# clouds_v30.net
KiCad netlist of a schematic drawn in EAGLE
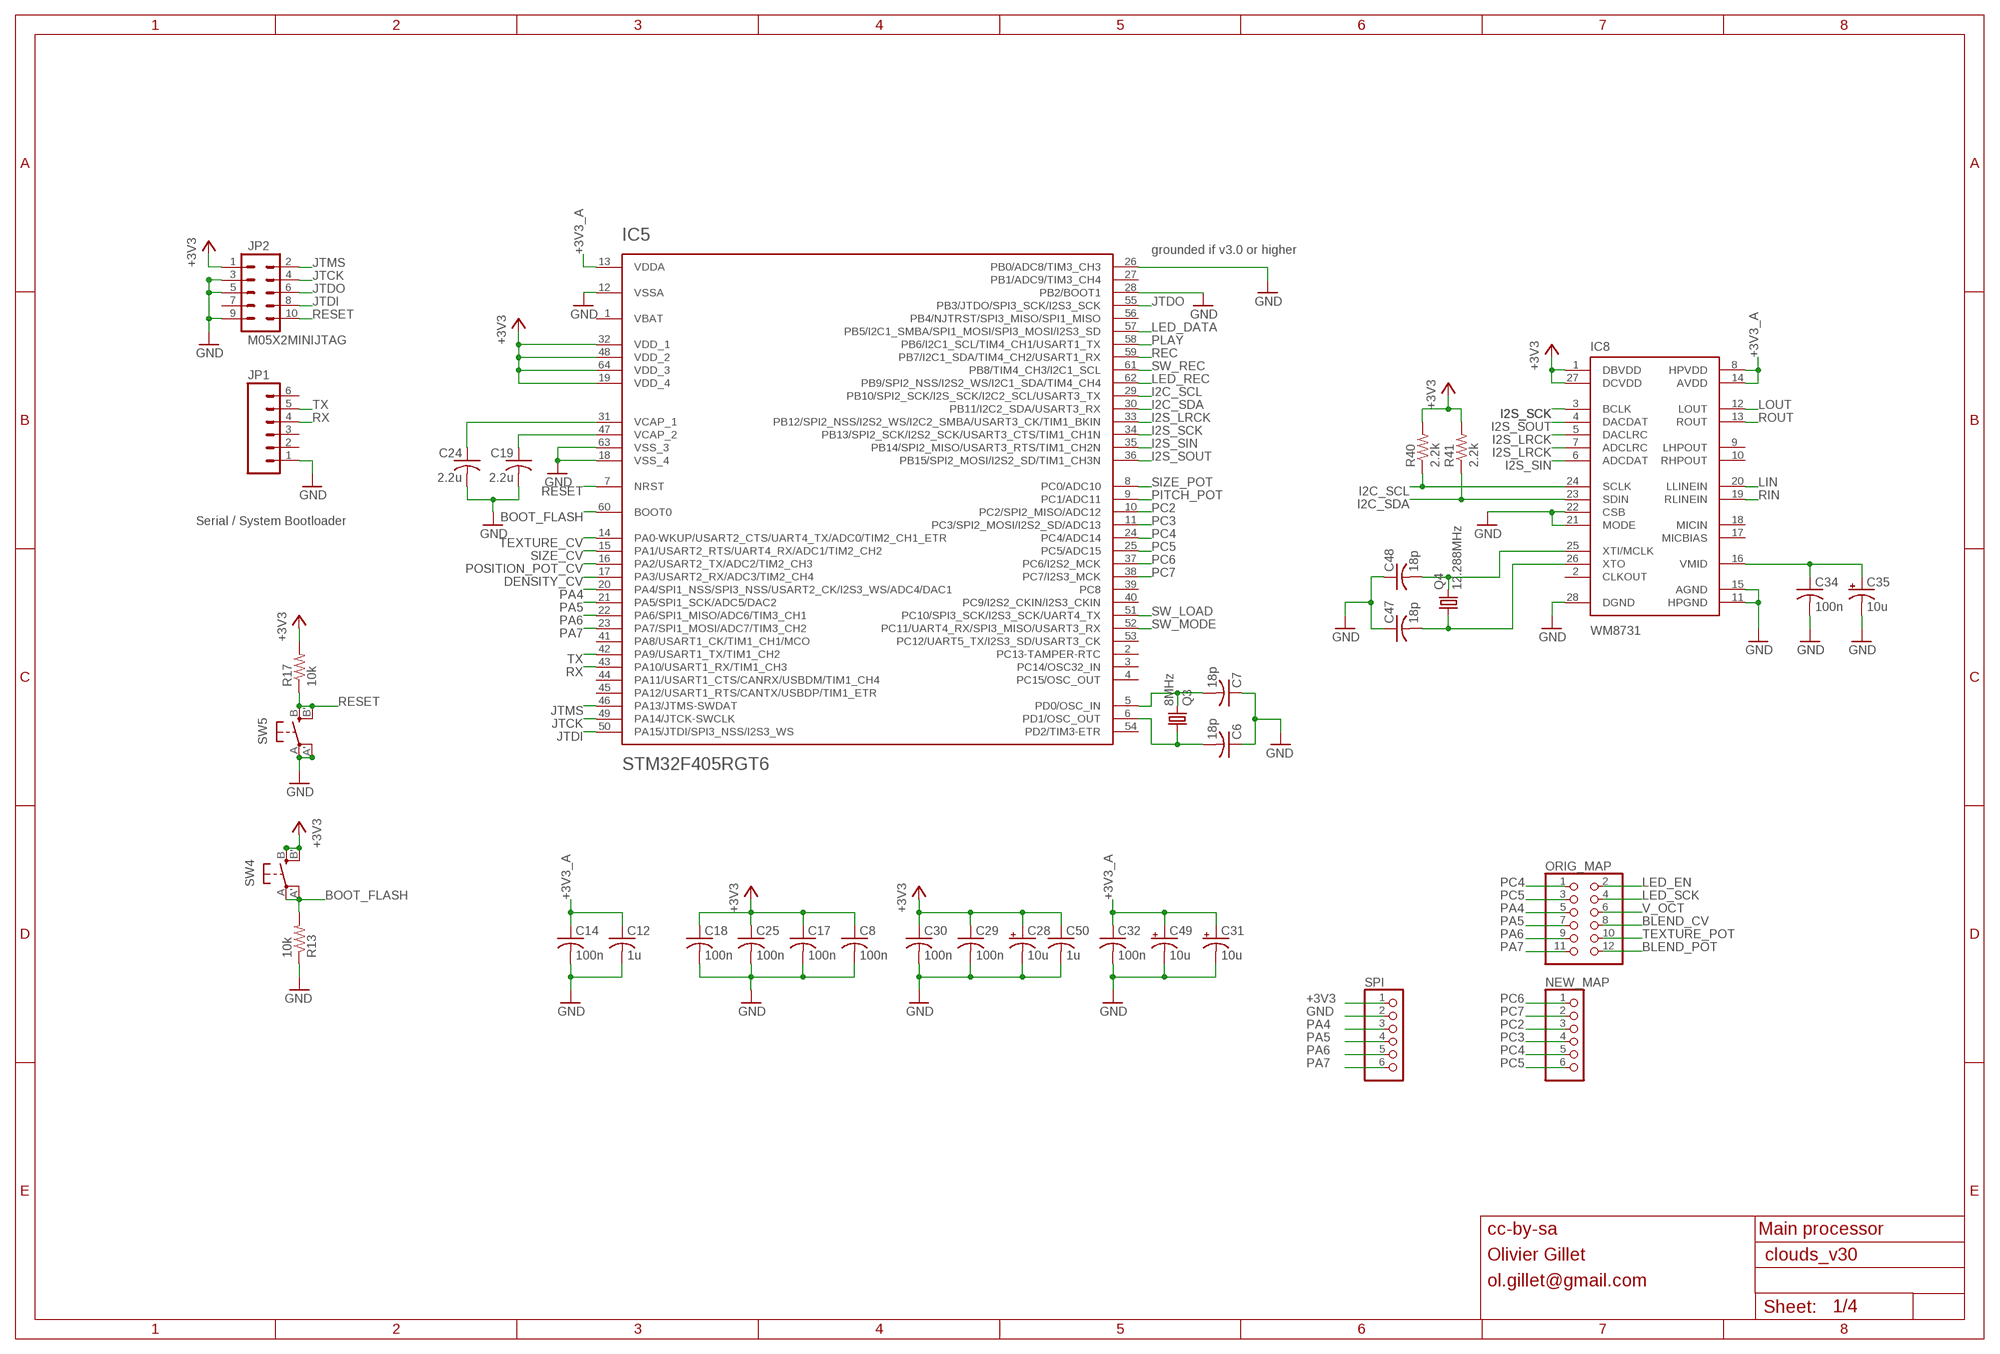
[diagram p0: schematic, sheet 1]
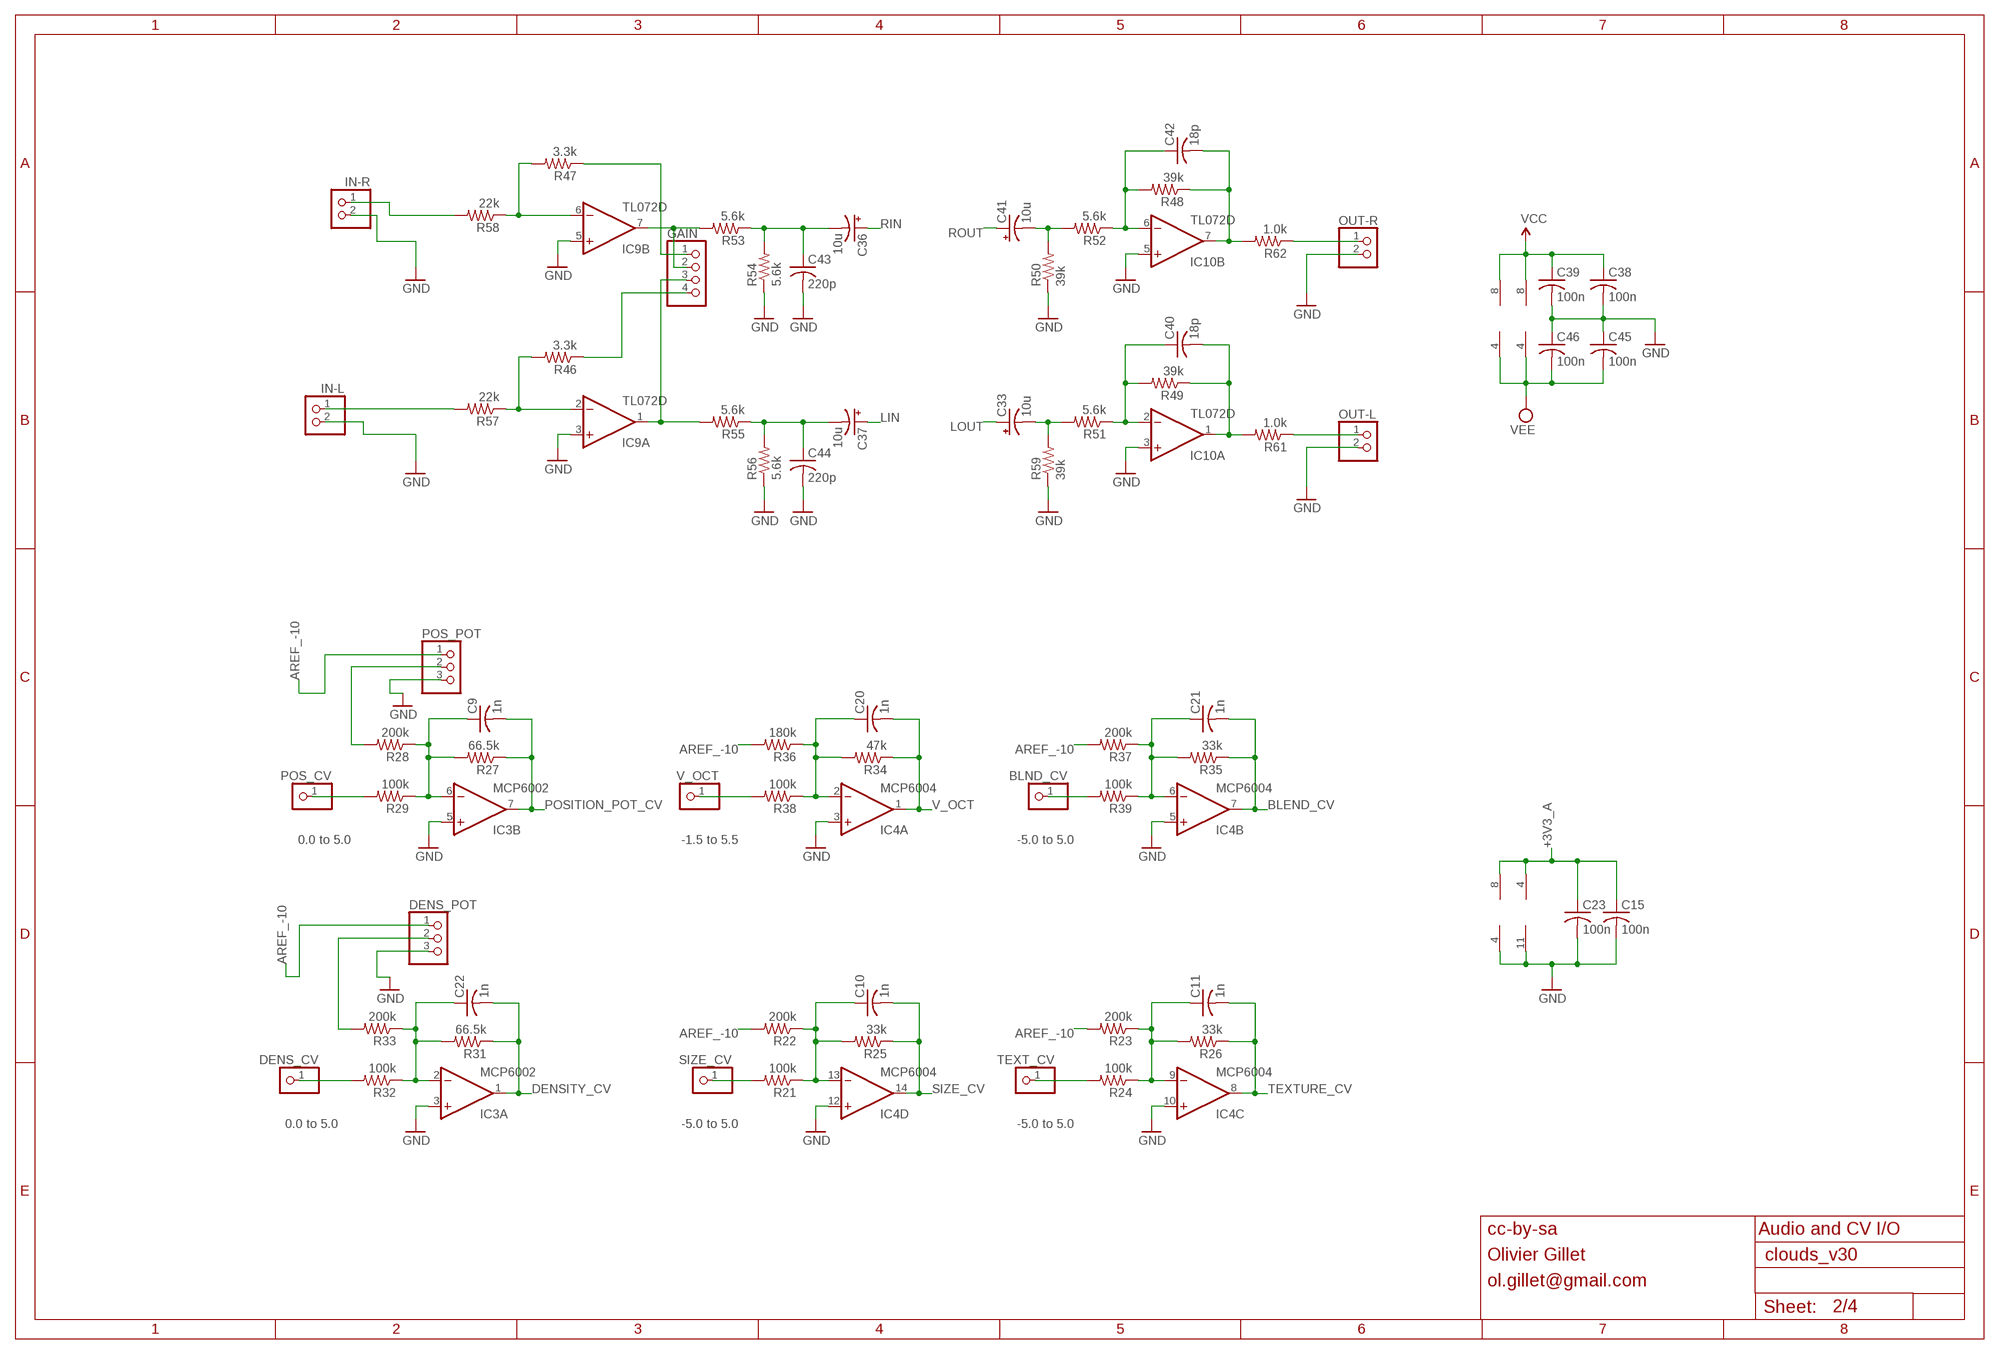
[diagram p1: schematic, sheet 2]
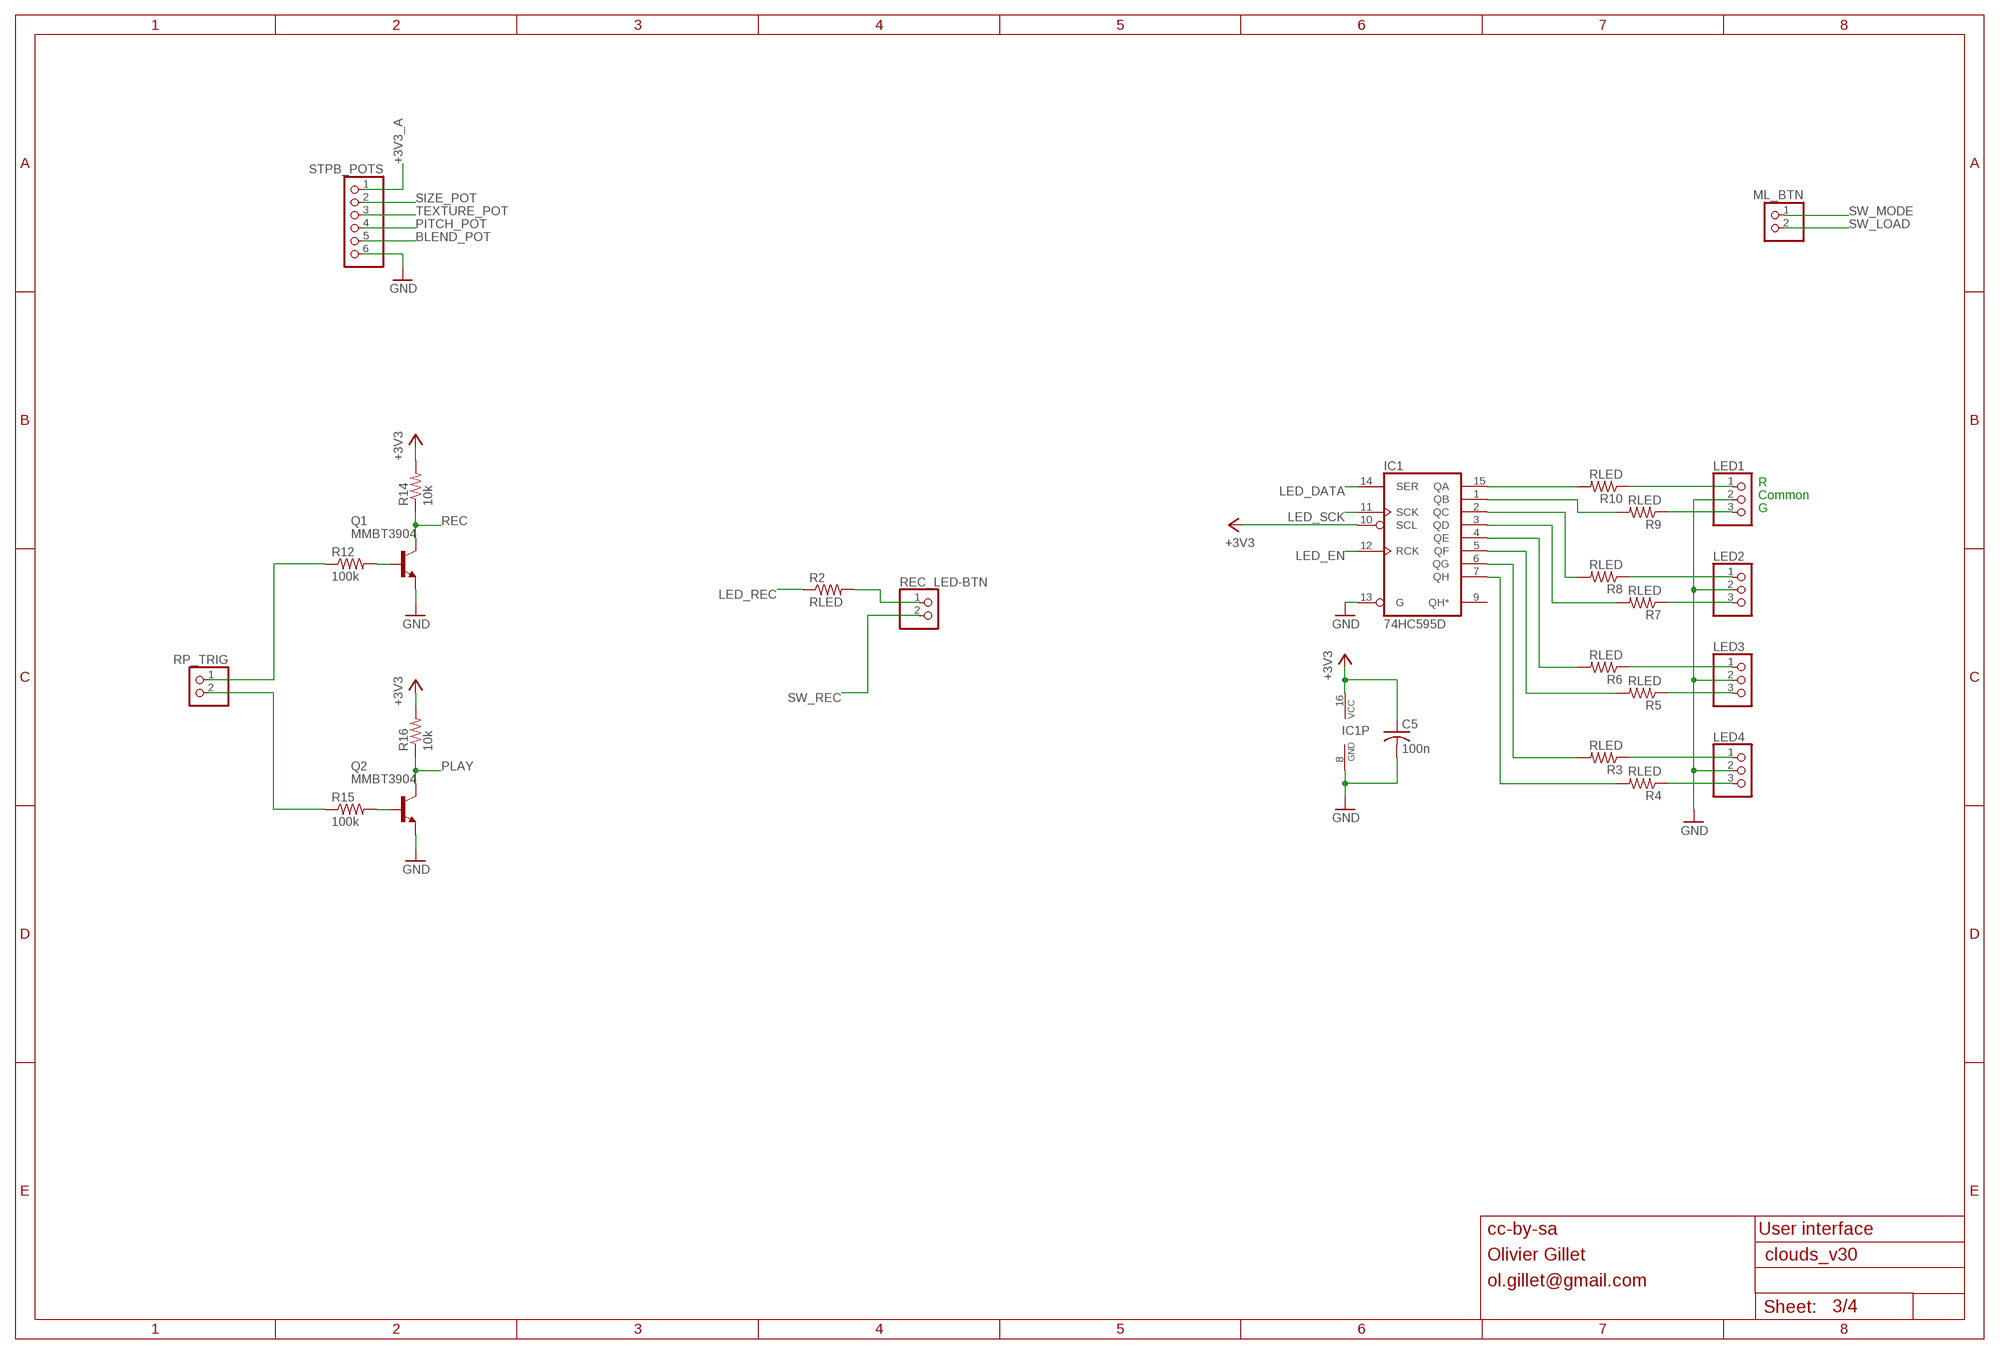
[diagram p2: schematic, sheet 3]
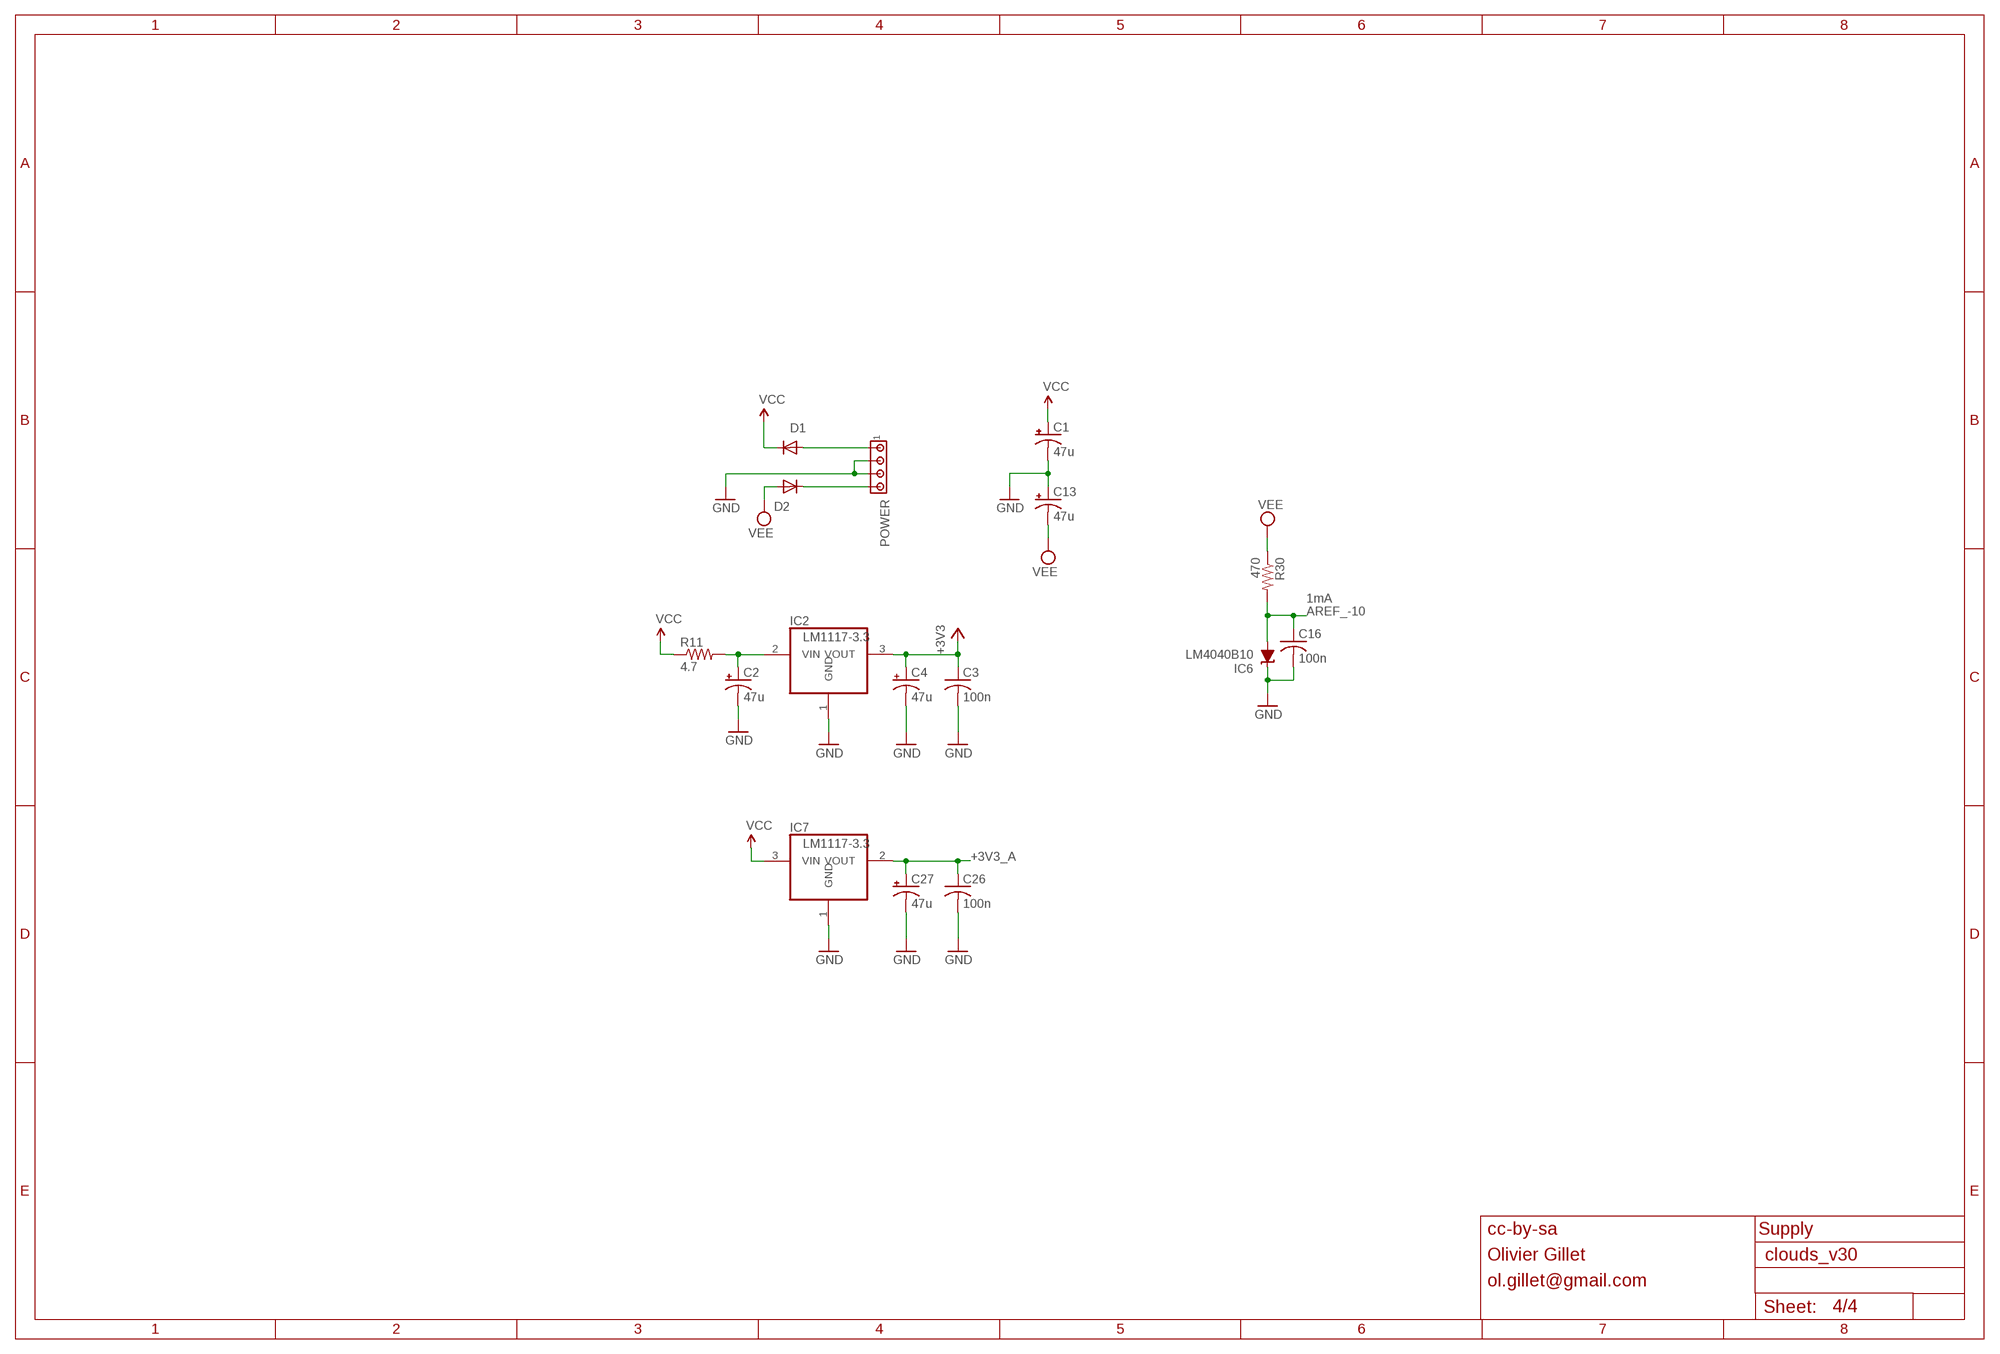
[diagram p3: schematic, sheet 4]

(export (version "E")
  (design (tool "Eeschema 10.0.6"))
  (components
    (comp (ref "C1")
      (value "47u")
      (footprint "eagle-import:PANASONIC_D")
      (libsource (lib "eagle-import") (part "CPOL-USD"))
    )
    (comp (ref "C2")
      (value "47u")
      (footprint "eagle-import:PANASONIC_D")
      (libsource (lib "eagle-import") (part "CPOL-USD"))
    )
    (comp (ref "C3")
      (value "100n")
      (footprint "eagle-import:C0603")
      (libsource (lib "eagle-import") (part "C-USC0603"))
    )
    (comp (ref "C4")
      (value "47u")
      (footprint "eagle-import:PANASONIC_D")
      (libsource (lib "eagle-import") (part "CPOL-USD"))
    )
    (comp (ref "C13")
      (value "47u")
      (footprint "eagle-import:PANASONIC_D")
      (libsource (lib "eagle-import") (part "CPOL-USD"))
    )
    (comp (ref "C16")
      (value "100n")
      (footprint "eagle-import:C0603")
      (libsource (lib "eagle-import") (part "C-USC0603"))
    )
    (comp (ref "C26")
      (value "100n")
      (footprint "eagle-import:C0603")
      (libsource (lib "eagle-import") (part "C-USC0603"))
    )
    (comp (ref "C27")
      (value "47u")
      (footprint "eagle-import:PANASONIC_D")
      (libsource (lib "eagle-import") (part "CPOL-USD"))
    )
    (comp (ref "D1")
      (value "1N5819HW")
      (footprint "eagle-import:SOD123")
      (libsource (lib "eagle-import") (part "DIODE-SOD123"))
    )
    (comp (ref "D2")
      (value "1N5819HW")
      (footprint "eagle-import:SOD123")
      (libsource (lib "eagle-import") (part "DIODE-SOD123"))
    )
    (comp (ref "IC2")
      (value "LM1117-3.3")
      (footprint "eagle-import:TO252")
      (libsource (lib "eagle-import") (part "REG1117T"))
    )
    (comp (ref "IC6")
      (value "LM4040B10")
      (footprint "eagle-import:DBZ_R-PDSO-G3")
      (libsource (lib "eagle-import") (part "LM4041DBZB12"))
    )
    (comp (ref "IC7")
      (value "LM1117-3.3")
      (footprint "eagle-import:SOT223")
      (libsource (lib "eagle-import") (part "REG1117"))
    )
    (comp (ref "POWER")
      (value "MTA04-156")
      (footprint "eagle-import:1X4MTA")
      (libsource (lib "eagle-import") (part "MTA04-156"))
    )
    (comp (ref "R11")
      (value "4.7")
      (footprint "eagle-import:R1206")
      (libsource (lib "eagle-import") (part "R-US_R1206"))
    )
    (comp (ref "R30")
      (value "470")
      (footprint "eagle-import:R0603")
      (libsource (lib "eagle-import") (part "R-US_R0603"))
    )
    (comp (ref "BLND_CV")
      (value "PINHD-1X1")
      (footprint "eagle-import:1X01")
      (libsource (lib "eagle-import") (part "PINHD-1X1"))
    )
    (comp (ref "C9")
      (value "1n")
      (footprint "eagle-import:C0603")
      (libsource (lib "eagle-import") (part "C-USC0603"))
    )
    (comp (ref "C10")
      (value "1n")
      (footprint "eagle-import:C0603")
      (libsource (lib "eagle-import") (part "C-USC0603"))
    )
    (comp (ref "C11")
      (value "1n")
      (footprint "eagle-import:C0603")
      (libsource (lib "eagle-import") (part "C-USC0603"))
    )
    (comp (ref "C15")
      (value "100n")
      (footprint "eagle-import:C0603")
      (libsource (lib "eagle-import") (part "C-USC0603"))
    )
    (comp (ref "C20")
      (value "1n")
      (footprint "eagle-import:C0603")
      (libsource (lib "eagle-import") (part "C-USC0603"))
    )
    (comp (ref "C21")
      (value "1n")
      (footprint "eagle-import:C0603")
      (libsource (lib "eagle-import") (part "C-USC0603"))
    )
    (comp (ref "C22")
      (value "1n")
      (footprint "eagle-import:C0603")
      (libsource (lib "eagle-import") (part "C-USC0603"))
    )
    (comp (ref "C23")
      (value "100n")
      (footprint "eagle-import:C0603")
      (libsource (lib "eagle-import") (part "C-USC0603"))
    )
    (comp (ref "C33")
      (value "10u")
      (footprint "eagle-import:PANASONIC_B")
      (libsource (lib "eagle-import") (part "CPOL-USB"))
    )
    (comp (ref "C36")
      (value "10u")
      (footprint "eagle-import:PANASONIC_B")
      (libsource (lib "eagle-import") (part "CPOL-USB"))
    )
    (comp (ref "C37")
      (value "10u")
      (footprint "eagle-import:PANASONIC_B")
      (libsource (lib "eagle-import") (part "CPOL-USB"))
    )
    (comp (ref "C38")
      (value "100n")
      (footprint "eagle-import:C0603")
      (libsource (lib "eagle-import") (part "C-USC0603"))
    )
    (comp (ref "C39")
      (value "100n")
      (footprint "eagle-import:C0603")
      (libsource (lib "eagle-import") (part "C-USC0603"))
    )
    (comp (ref "C40")
      (value "18p")
      (footprint "eagle-import:C0603")
      (libsource (lib "eagle-import") (part "C-USC0603"))
    )
    (comp (ref "C41")
      (value "10u")
      (footprint "eagle-import:PANASONIC_B")
      (libsource (lib "eagle-import") (part "CPOL-USB"))
    )
    (comp (ref "C42")
      (value "18p")
      (footprint "eagle-import:C0603")
      (libsource (lib "eagle-import") (part "C-USC0603"))
    )
    (comp (ref "C43")
      (value "220p")
      (footprint "eagle-import:C0603")
      (libsource (lib "eagle-import") (part "C-USC0603"))
    )
    (comp (ref "C44")
      (value "220p")
      (footprint "eagle-import:C0603")
      (libsource (lib "eagle-import") (part "C-USC0603"))
    )
    (comp (ref "C45")
      (value "100n")
      (footprint "eagle-import:C0603")
      (libsource (lib "eagle-import") (part "C-USC0603"))
    )
    (comp (ref "C46")
      (value "100n")
      (footprint "eagle-import:C0603")
      (libsource (lib "eagle-import") (part "C-USC0603"))
    )
    (comp (ref "DENS_CV")
      (value "PINHD-1X1")
      (footprint "eagle-import:1X01")
      (libsource (lib "eagle-import") (part "PINHD-1X1"))
    )
    (comp (ref "DENS_POT")
      (value "PINHD-1X3")
      (footprint "eagle-import:1X03")
      (libsource (lib "eagle-import") (part "PINHD-1X3"))
    )
    (comp (ref "GAIN")
      (value "PINHD-1X4")
      (footprint "eagle-import:1X04")
      (libsource (lib "eagle-import") (part "PINHD-1X4"))
    )
    (comp (ref "IC3")
      (value "MCP6002")
      (footprint "eagle-import:SO08")
      (libsource (lib "eagle-import") (part "TL072D"))
    )
    (comp (ref "IC4")
      (value "MCP6004")
      (footprint "eagle-import:SO14")
      (libsource (lib "eagle-import") (part "TL074D"))
    )
    (comp (ref "IC9")
      (value "TL072D")
      (footprint "eagle-import:SO08")
      (libsource (lib "eagle-import") (part "og-linear_TL072D"))
    )
    (comp (ref "IC10")
      (value "TL072D")
      (footprint "eagle-import:SO08")
      (libsource (lib "eagle-import") (part "og-linear_TL072D"))
    )
    (comp (ref "IN-L")
      (value "PINHD-1X2")
      (footprint "eagle-import:1X02")
      (libsource (lib "eagle-import") (part "PINHD-1X2"))
    )
    (comp (ref "IN-R")
      (value "PINHD-1X2")
      (footprint "eagle-import:1X02")
      (libsource (lib "eagle-import") (part "PINHD-1X2"))
    )
    (comp (ref "OUT-L")
      (value "PINHD-1X2")
      (footprint "eagle-import:1X02")
      (libsource (lib "eagle-import") (part "PINHD-1X2"))
    )
    (comp (ref "OUT-R")
      (value "PINHD-1X2")
      (footprint "eagle-import:1X02")
      (libsource (lib "eagle-import") (part "PINHD-1X2"))
    )
    (comp (ref "POS_CV")
      (value "PINHD-1X1")
      (footprint "eagle-import:1X01")
      (libsource (lib "eagle-import") (part "PINHD-1X1"))
    )
    (comp (ref "POS_POT")
      (value "PINHD-1X3")
      (footprint "eagle-import:1X03")
      (libsource (lib "eagle-import") (part "PINHD-1X3"))
    )
    (comp (ref "R21")
      (value "100k")
      (footprint "eagle-import:R0603")
      (libsource (lib "eagle-import") (part "R-US_R0603"))
    )
    (comp (ref "R22")
      (value "200k")
      (footprint "eagle-import:R0603")
      (libsource (lib "eagle-import") (part "R-US_R0603"))
    )
    (comp (ref "R23")
      (value "200k")
      (footprint "eagle-import:R0603")
      (libsource (lib "eagle-import") (part "R-US_R0603"))
    )
    (comp (ref "R24")
      (value "100k")
      (footprint "eagle-import:R0603")
      (libsource (lib "eagle-import") (part "R-US_R0603"))
    )
    (comp (ref "R25")
      (value "33k")
      (footprint "eagle-import:R0603")
      (libsource (lib "eagle-import") (part "R-US_R0603"))
    )
    (comp (ref "R26")
      (value "33k")
      (footprint "eagle-import:R0603")
      (libsource (lib "eagle-import") (part "R-US_R0603"))
    )
    (comp (ref "R27")
      (value "66.5k")
      (footprint "eagle-import:R0603")
      (libsource (lib "eagle-import") (part "R-US_R0603"))
    )
    (comp (ref "R28")
      (value "200k")
      (footprint "eagle-import:R0603")
      (libsource (lib "eagle-import") (part "R-US_R0603"))
    )
    (comp (ref "R29")
      (value "100k")
      (footprint "eagle-import:R0603")
      (libsource (lib "eagle-import") (part "R-US_R0603"))
    )
    (comp (ref "R31")
      (value "66.5k")
      (footprint "eagle-import:R0603")
      (libsource (lib "eagle-import") (part "R-US_R0603"))
    )
    (comp (ref "R32")
      (value "100k")
      (footprint "eagle-import:R0603")
      (libsource (lib "eagle-import") (part "R-US_R0603"))
    )
    (comp (ref "R33")
      (value "200k")
      (footprint "eagle-import:R0603")
      (libsource (lib "eagle-import") (part "R-US_R0603"))
    )
    (comp (ref "R34")
      (value "47k")
      (footprint "eagle-import:R0603")
      (libsource (lib "eagle-import") (part "R-US_R0603"))
    )
    (comp (ref "R35")
      (value "33k")
      (footprint "eagle-import:R0603")
      (libsource (lib "eagle-import") (part "R-US_R0603"))
    )
    (comp (ref "R36")
      (value "180k")
      (footprint "eagle-import:R0603")
      (libsource (lib "eagle-import") (part "R-US_R0603"))
    )
    (comp (ref "R37")
      (value "200k")
      (footprint "eagle-import:R0603")
      (libsource (lib "eagle-import") (part "R-US_R0603"))
    )
    (comp (ref "R38")
      (value "100k")
      (footprint "eagle-import:R0603")
      (libsource (lib "eagle-import") (part "R-US_R0603"))
    )
    (comp (ref "R39")
      (value "100k")
      (footprint "eagle-import:R0603")
      (libsource (lib "eagle-import") (part "R-US_R0603"))
    )
    (comp (ref "R46")
      (value "3.3k")
      (footprint "eagle-import:R0603")
      (libsource (lib "eagle-import") (part "R-US_R0603"))
    )
    (comp (ref "R47")
      (value "3.3k")
      (footprint "eagle-import:R0603")
      (libsource (lib "eagle-import") (part "R-US_R0603"))
    )
    (comp (ref "R48")
      (value "39k")
      (footprint "eagle-import:R0603")
      (libsource (lib "eagle-import") (part "R-US_R0603"))
    )
    (comp (ref "R49")
      (value "39k")
      (footprint "eagle-import:R0603")
      (libsource (lib "eagle-import") (part "R-US_R0603"))
    )
    (comp (ref "R50")
      (value "39k")
      (footprint "eagle-import:R0603")
      (libsource (lib "eagle-import") (part "R-US_R0603"))
    )
    (comp (ref "R51")
      (value "5.6k")
      (footprint "eagle-import:R0603")
      (libsource (lib "eagle-import") (part "R-US_R0603"))
    )
    (comp (ref "R52")
      (value "5.6k")
      (footprint "eagle-import:R0603")
      (libsource (lib "eagle-import") (part "R-US_R0603"))
    )
    (comp (ref "R53")
      (value "5.6k")
      (footprint "eagle-import:R0603")
      (libsource (lib "eagle-import") (part "R-US_R0603"))
    )
    (comp (ref "R54")
      (value "5.6k")
      (footprint "eagle-import:R0603")
      (libsource (lib "eagle-import") (part "R-US_R0603"))
    )
    (comp (ref "R55")
      (value "5.6k")
      (footprint "eagle-import:R0603")
      (libsource (lib "eagle-import") (part "R-US_R0603"))
    )
    (comp (ref "R56")
      (value "5.6k")
      (footprint "eagle-import:R0603")
      (libsource (lib "eagle-import") (part "R-US_R0603"))
    )
    (comp (ref "R57")
      (value "22k")
      (footprint "eagle-import:R0603")
      (libsource (lib "eagle-import") (part "R-US_R0603"))
    )
    (comp (ref "R58")
      (value "22k")
      (footprint "eagle-import:R0603")
      (libsource (lib "eagle-import") (part "R-US_R0603"))
    )
    (comp (ref "R59")
      (value "39k")
      (footprint "eagle-import:R0603")
      (libsource (lib "eagle-import") (part "R-US_R0603"))
    )
    (comp (ref "R61")
      (value "1.0k")
      (footprint "eagle-import:R0603")
      (libsource (lib "eagle-import") (part "R-US_R0603"))
    )
    (comp (ref "R62")
      (value "1.0k")
      (footprint "eagle-import:R0603")
      (libsource (lib "eagle-import") (part "R-US_R0603"))
    )
    (comp (ref "SIZE_CV")
      (value "PINHD-1X1")
      (footprint "eagle-import:1X01")
      (libsource (lib "eagle-import") (part "PINHD-1X1"))
    )
    (comp (ref "TEXT_CV")
      (value "PINHD-1X1")
      (footprint "eagle-import:1X01")
      (libsource (lib "eagle-import") (part "PINHD-1X1"))
    )
    (comp (ref "V_OCT")
      (value "PINHD-1X1")
      (footprint "eagle-import:1X01")
      (libsource (lib "eagle-import") (part "PINHD-1X1"))
    )
    (comp (ref "C6")
      (value "18p")
      (footprint "eagle-import:C0603")
      (libsource (lib "eagle-import") (part "C-USC0603"))
    )
    (comp (ref "C7")
      (value "18p")
      (footprint "eagle-import:C0603")
      (libsource (lib "eagle-import") (part "C-USC0603"))
    )
    (comp (ref "C8")
      (value "100n")
      (footprint "eagle-import:C0603")
      (libsource (lib "eagle-import") (part "C-USC0603"))
    )
    (comp (ref "C12")
      (value "1u")
      (footprint "eagle-import:C0603")
      (libsource (lib "eagle-import") (part "C-USC0603"))
    )
    (comp (ref "C14")
      (value "100n")
      (footprint "eagle-import:C0603")
      (libsource (lib "eagle-import") (part "C-USC0603"))
    )
    (comp (ref "C17")
      (value "100n")
      (footprint "eagle-import:C0603")
      (libsource (lib "eagle-import") (part "C-USC0603"))
    )
    (comp (ref "C18")
      (value "100n")
      (footprint "eagle-import:C0603")
      (libsource (lib "eagle-import") (part "C-USC0603"))
    )
    (comp (ref "C19")
      (value "2.2u")
      (footprint "eagle-import:C0805")
      (libsource (lib "eagle-import") (part "C-USC0805"))
    )
    (comp (ref "C24")
      (value "2.2u")
      (footprint "eagle-import:C0805")
      (libsource (lib "eagle-import") (part "C-USC0805"))
    )
    (comp (ref "C25")
      (value "100n")
      (footprint "eagle-import:C0603")
      (libsource (lib "eagle-import") (part "C-USC0603"))
    )
    (comp (ref "C28")
      (value "10u")
      (footprint "eagle-import:PANASONIC_A")
      (libsource (lib "eagle-import") (part "CPOL-USA"))
    )
    (comp (ref "C29")
      (value "100n")
      (footprint "eagle-import:C0603")
      (libsource (lib "eagle-import") (part "C-USC0603"))
    )
    (comp (ref "C30")
      (value "100n")
      (footprint "eagle-import:C0603")
      (libsource (lib "eagle-import") (part "C-USC0603"))
    )
    (comp (ref "C31")
      (value "10u")
      (footprint "eagle-import:PANASONIC_B")
      (libsource (lib "eagle-import") (part "CPOL-USB"))
    )
    (comp (ref "C32")
      (value "100n")
      (footprint "eagle-import:C0603")
      (libsource (lib "eagle-import") (part "C-USC0603"))
    )
    (comp (ref "C34")
      (value "100n")
      (footprint "eagle-import:C0603")
      (libsource (lib "eagle-import") (part "C-USC0603"))
    )
    (comp (ref "C35")
      (value "10u")
      (footprint "eagle-import:PANASONIC_B")
      (libsource (lib "eagle-import") (part "CPOL-USB"))
    )
    (comp (ref "C47")
      (value "18p")
      (footprint "eagle-import:C0603")
      (libsource (lib "eagle-import") (part "C-USC0603"))
    )
    (comp (ref "C48")
      (value "18p")
      (footprint "eagle-import:C0603")
      (libsource (lib "eagle-import") (part "C-USC0603"))
    )
    (comp (ref "C49")
      (value "10u")
      (footprint "eagle-import:PANASONIC_A")
      (libsource (lib "eagle-import") (part "CPOL-USA"))
    )
    (comp (ref "C50")
      (value "1u")
      (footprint "eagle-import:C0603")
      (libsource (lib "eagle-import") (part "C-USC0603"))
    )
    (comp (ref "IC5")
      (value "STM32F405RGT6")
      (footprint "eagle-import:TQFP-10X10-64")
      (libsource (lib "eagle-import") (part "STM32F20X"))
    )
    (comp (ref "IC8")
      (value "WM8731")
      (footprint "eagle-import:SSOP28")
      (libsource (lib "eagle-import") (part "WM8731"))
    )
    (comp (ref "JP1")
      (value "M06SIP")
      (footprint "eagle-import:1X06")
      (libsource (lib "eagle-import") (part "M06SIP"))
    )
    (comp (ref "JP2")
      (value "M05X2MINIJTAG")
      (footprint "eagle-import:2X5-1.27")
      (libsource (lib "eagle-import") (part "M05X2MINIJTAG"))
    )
    (comp (ref "NEW_MAP")
      (value "PINHD-1X6")
      (footprint "eagle-import:1X06")
      (libsource (lib "eagle-import") (part "PINHD-1X6"))
    )
    (comp (ref "ORIG_MAP")
      (value "PINHD-2X6")
      (footprint "eagle-import:2X06")
      (libsource (lib "eagle-import") (part "PINHD-2X6"))
    )
    (comp (ref "Q3")
      (value "8MHz")
      (footprint "eagle-import:HC49UP")
      (libsource (lib "eagle-import") (part "CRYSTALHC49UP"))
    )
    (comp (ref "Q4")
      (value "12.288MHz")
      (footprint "eagle-import:HC49UP")
      (libsource (lib "eagle-import") (part "CRYSTALHC49UP"))
    )
    (comp (ref "R13")
      (value "10k")
      (footprint "eagle-import:R0603")
      (libsource (lib "eagle-import") (part "R-US_R0603"))
    )
    (comp (ref "R17")
      (value "10k")
      (footprint "eagle-import:R0603")
      (libsource (lib "eagle-import") (part "R-US_R0603"))
    )
    (comp (ref "R40")
      (value "2.2k")
      (footprint "eagle-import:R0603")
      (libsource (lib "eagle-import") (part "R-US_R0603"))
    )
    (comp (ref "R41")
      (value "2.2k")
      (footprint "eagle-import:R0603")
      (libsource (lib "eagle-import") (part "R-US_R0603"))
    )
    (comp (ref "SPI")
      (value "PINHD-1X6")
      (footprint "eagle-import:1X06")
      (libsource (lib "eagle-import") (part "PINHD-1X6"))
    )
    (comp (ref "SW4")
      (value "EVQQ2")
      (footprint "eagle-import:EVQ-Q2")
      (libsource (lib "eagle-import") (part "EVQQ2"))
    )
    (comp (ref "SW5")
      (value "EVQQ2")
      (footprint "eagle-import:EVQ-Q2")
      (libsource (lib "eagle-import") (part "EVQQ2"))
    )
    (comp (ref "C5")
      (value "100n")
      (footprint "eagle-import:C0603")
      (libsource (lib "eagle-import") (part "C-USC0603"))
    )
    (comp (ref "IC1")
      (value "74HC595D")
      (footprint "eagle-import:SO16")
      (libsource (lib "eagle-import") (part "74595DHC"))
    )
    (comp (ref "LED1")
      (value "PINHD-1X3")
      (footprint "eagle-import:1X03")
      (libsource (lib "eagle-import") (part "PINHD-1X3"))
    )
    (comp (ref "LED2")
      (value "PINHD-1X3")
      (footprint "eagle-import:1X03")
      (libsource (lib "eagle-import") (part "PINHD-1X3"))
    )
    (comp (ref "LED3")
      (value "PINHD-1X3")
      (footprint "eagle-import:1X03")
      (libsource (lib "eagle-import") (part "PINHD-1X3"))
    )
    (comp (ref "LED4")
      (value "PINHD-1X3")
      (footprint "eagle-import:1X03")
      (libsource (lib "eagle-import") (part "PINHD-1X3"))
    )
    (comp (ref "ML_BTN")
      (value "PINHD-1X2")
      (footprint "eagle-import:1X02")
      (libsource (lib "eagle-import") (part "PINHD-1X2"))
    )
    (comp (ref "Q1")
      (value "MMBT3904")
      (footprint "eagle-import:SOT23-BEC")
      (libsource (lib "eagle-import") (part "-NPN-SOT23-BECMMBT3904LT1"))
    )
    (comp (ref "Q2")
      (value "MMBT3904")
      (footprint "eagle-import:SOT23-BEC")
      (libsource (lib "eagle-import") (part "-NPN-SOT23-BECMMBT3904LT1"))
    )
    (comp (ref "R2")
      (value "RLED")
      (footprint "eagle-import:R0603")
      (libsource (lib "eagle-import") (part "R-US_R0603"))
    )
    (comp (ref "R3")
      (value "RLED")
      (footprint "eagle-import:R0603")
      (libsource (lib "eagle-import") (part "R-US_R0603"))
    )
    (comp (ref "R4")
      (value "RLED")
      (footprint "eagle-import:R0603")
      (libsource (lib "eagle-import") (part "R-US_R0603"))
    )
    (comp (ref "R5")
      (value "RLED")
      (footprint "eagle-import:R0603")
      (libsource (lib "eagle-import") (part "R-US_R0603"))
    )
    (comp (ref "R6")
      (value "RLED")
      (footprint "eagle-import:R0603")
      (libsource (lib "eagle-import") (part "R-US_R0603"))
    )
    (comp (ref "R7")
      (value "RLED")
      (footprint "eagle-import:R0603")
      (libsource (lib "eagle-import") (part "R-US_R0603"))
    )
    (comp (ref "R8")
      (value "RLED")
      (footprint "eagle-import:R0603")
      (libsource (lib "eagle-import") (part "R-US_R0603"))
    )
    (comp (ref "R9")
      (value "RLED")
      (footprint "eagle-import:R0603")
      (libsource (lib "eagle-import") (part "R-US_R0603"))
    )
    (comp (ref "R10")
      (value "RLED")
      (footprint "eagle-import:R0603")
      (libsource (lib "eagle-import") (part "R-US_R0603"))
    )
    (comp (ref "R12")
      (value "100k")
      (footprint "eagle-import:R0603")
      (libsource (lib "eagle-import") (part "R-US_R0603"))
    )
    (comp (ref "R14")
      (value "10k")
      (footprint "eagle-import:R0603")
      (libsource (lib "eagle-import") (part "R-US_R0603"))
    )
    (comp (ref "R15")
      (value "100k")
      (footprint "eagle-import:R0603")
      (libsource (lib "eagle-import") (part "R-US_R0603"))
    )
    (comp (ref "R16")
      (value "10k")
      (footprint "eagle-import:R0603")
      (libsource (lib "eagle-import") (part "R-US_R0603"))
    )
    (comp (ref "REC_LED-BTN")
      (value "PINHD-1X2")
      (footprint "eagle-import:1X02")
      (libsource (lib "eagle-import") (part "PINHD-1X2"))
    )
    (comp (ref "RP_TRIG")
      (value "PINHD-1X2")
      (footprint "eagle-import:1X02")
      (libsource (lib "eagle-import") (part "PINHD-1X2"))
    )
    (comp (ref "STPB_POTS")
      (value "PINHD-1X6")
      (footprint "eagle-import:1X06")
      (libsource (lib "eagle-import") (part "PINHD-1X6"))
    )
  )
  (nets
    (net (code "1") (name "+3V3") (class "Default")
      (node (ref "C17") (pin "1") (pinfunction "1_1") (pintype "passive"))
      (node (ref "C18") (pin "1") (pinfunction "1_1") (pintype "passive"))
      (node (ref "C25") (pin "1") (pinfunction "1_1") (pintype "passive"))
      (node (ref "C28") (pin "+") (pinfunction "+_+") (pintype "passive"))
      (node (ref "C29") (pin "1") (pinfunction "1_1") (pintype "passive"))
      (node (ref "C3") (pin "1") (pinfunction "1_1") (pintype "passive"))
      (node (ref "C30") (pin "1") (pinfunction "1_1") (pintype "passive"))
      (node (ref "C4") (pin "+") (pinfunction "+_+") (pintype "passive"))
      (node (ref "C5") (pin "1") (pinfunction "1_1") (pintype "passive"))
      (node (ref "C50") (pin "1") (pinfunction "1_1") (pintype "passive"))
      (node (ref "C8") (pin "1") (pinfunction "1_1") (pintype "passive"))
      (node (ref "IC1") (pin "10") (pinfunction "SCL_10") (pintype "input"))
      (node (ref "IC1") (pin "16") (pinfunction "VCC_16") (pintype "power_in"))
      (node (ref "IC2") (pin "3") (pinfunction "VOUT_3") (pintype "output"))
      (node (ref "IC5") (pin "19") (pinfunction "VDD_4_19") (pintype "power_in"))
      (node (ref "IC5") (pin "32") (pinfunction "VDD_1_32") (pintype "power_in"))
      (node (ref "IC5") (pin "48") (pinfunction "VDD_2_48") (pintype "power_in"))
      (node (ref "IC5") (pin "64") (pinfunction "VDD_3_64") (pintype "power_in"))
      (node (ref "IC8") (pin "1") (pinfunction "DBVDD_1") (pintype "bidirectional"))
      (node (ref "IC8") (pin "27") (pinfunction "DCVDD_27") (pintype "bidirectional"))
      (node (ref "JP2") (pin "1") (pinfunction "1_1") (pintype "passive"))
      (node (ref "R14") (pin "2") (pinfunction "2_2") (pintype "passive"))
      (node (ref "R16") (pin "2") (pinfunction "2_2") (pintype "passive"))
      (node (ref "R17") (pin "2") (pinfunction "2_2") (pintype "passive"))
      (node (ref "R40") (pin "2") (pinfunction "2_2") (pintype "passive"))
      (node (ref "R41") (pin "2") (pinfunction "2_2") (pintype "passive"))
      (node (ref "SPI") (pin "1") (pinfunction "1_1") (pintype "passive"))
      (node (ref "SW4") (pin "B") (pinfunction "S_B") (pintype "passive"))
      (node (ref "SW4") (pin "B'") (pinfunction "S1_B'") (pintype "passive"))
    )
    (net (code "2") (name "+3V3_A") (class "Default")
      (node (ref "C12") (pin "1") (pinfunction "1_1") (pintype "passive"))
      (node (ref "C14") (pin "1") (pinfunction "1_1") (pintype "passive"))
      (node (ref "C15") (pin "1") (pinfunction "1_1") (pintype "passive"))
      (node (ref "C23") (pin "1") (pinfunction "1_1") (pintype "passive"))
      (node (ref "C26") (pin "1") (pinfunction "1_1") (pintype "passive"))
      (node (ref "C27") (pin "+") (pinfunction "+_+") (pintype "passive"))
      (node (ref "C31") (pin "+") (pinfunction "+_+") (pintype "passive"))
      (node (ref "C32") (pin "1") (pinfunction "1_1") (pintype "passive"))
      (node (ref "C49") (pin "+") (pinfunction "+_+") (pintype "passive"))
      (node (ref "IC3") (pin "8") (pinfunction "V+_8") (pintype "power_in"))
      (node (ref "IC4") (pin "4") (pinfunction "V+_4") (pintype "power_in"))
      (node (ref "IC5") (pin "13") (pinfunction "VDDA_13") (pintype "power_in"))
      (node (ref "IC7") (pin "2") (pinfunction "VOUT_2") (pintype "output"))
      (node (ref "IC8") (pin "14") (pinfunction "AVDD_14") (pintype "bidirectional"))
      (node (ref "IC8") (pin "8") (pinfunction "HPVDD_8") (pintype "bidirectional"))
      (node (ref "STPB_POTS") (pin "1") (pinfunction "1_1") (pintype "passive"))
    )
    (net (code "3") (name "AREF_-10") (class "Default")
      (node (ref "C16") (pin "1") (pinfunction "1_1") (pintype "passive"))
      (node (ref "DENS_POT") (pin "1") (pinfunction "1_1") (pintype "passive"))
      (node (ref "IC6") (pin "2") (pinfunction "A_2") (pintype "passive"))
      (node (ref "POS_POT") (pin "1") (pinfunction "1_1") (pintype "passive"))
      (node (ref "R22") (pin "2") (pinfunction "2_2") (pintype "passive"))
      (node (ref "R23") (pin "2") (pinfunction "2_2") (pintype "passive"))
      (node (ref "R30") (pin "2") (pinfunction "2_2") (pintype "passive"))
      (node (ref "R36") (pin "2") (pinfunction "2_2") (pintype "passive"))
      (node (ref "R37") (pin "2") (pinfunction "2_2") (pintype "passive"))
    )
    (net (code "4") (name "BLEND_CV") (class "Default")
      (node (ref "C21") (pin "2") (pinfunction "2_2") (pintype "passive"))
      (node (ref "IC4") (pin "7") (pinfunction "OUT_7") (pintype "output"))
      (node (ref "ORIG_MAP") (pin "8") (pinfunction "8_8") (pintype "passive"))
      (node (ref "R35") (pin "1") (pinfunction "1_1") (pintype "passive"))
    )
    (net (code "5") (name "BLEND_POT") (class "Default")
      (node (ref "ORIG_MAP") (pin "12") (pinfunction "12_12") (pintype "passive"))
      (node (ref "STPB_POTS") (pin "5") (pinfunction "5_5") (pintype "passive"))
    )
    (net (code "6") (name "BOOT_FLASH") (class "Default")
      (node (ref "IC5") (pin "60") (pinfunction "BOOT0_60") (pintype "bidirectional"))
      (node (ref "R13") (pin "2") (pinfunction "2_2") (pintype "passive"))
      (node (ref "SW4") (pin "A") (pinfunction "P_A") (pintype "passive"))
      (node (ref "SW4") (pin "A'") (pinfunction "P1_A'") (pintype "passive"))
    )
    (net (code "7") (name "DENSITY_CV") (class "Default")
      (node (ref "C22") (pin "2") (pinfunction "2_2") (pintype "passive"))
      (node (ref "IC3") (pin "1") (pinfunction "OUT_1") (pintype "output"))
      (node (ref "IC5") (pin "17") (pinfunction "PA3/USART2_RX/ADC3/TIM2_CH4_17") (pintype "bidirectional"))
      (node (ref "R31") (pin "1") (pinfunction "1_1") (pintype "passive"))
    )
    (net (code "8") (name "GND") (class "Default")
      (node (ref "C1") (pin "-") (pinfunction "-_-") (pintype "passive"))
      (node (ref "C12") (pin "2") (pinfunction "2_2") (pintype "passive"))
      (node (ref "C13") (pin "+") (pinfunction "+_+") (pintype "passive"))
      (node (ref "C14") (pin "2") (pinfunction "2_2") (pintype "passive"))
      (node (ref "C15") (pin "2") (pinfunction "2_2") (pintype "passive"))
      (node (ref "C16") (pin "2") (pinfunction "2_2") (pintype "passive"))
      (node (ref "C17") (pin "2") (pinfunction "2_2") (pintype "passive"))
      (node (ref "C18") (pin "2") (pinfunction "2_2") (pintype "passive"))
      (node (ref "C19") (pin "2") (pinfunction "2_2") (pintype "passive"))
      (node (ref "C2") (pin "-") (pinfunction "-_-") (pintype "passive"))
      (node (ref "C23") (pin "2") (pinfunction "2_2") (pintype "passive"))
      (node (ref "C24") (pin "2") (pinfunction "2_2") (pintype "passive"))
      (node (ref "C25") (pin "2") (pinfunction "2_2") (pintype "passive"))
      (node (ref "C26") (pin "2") (pinfunction "2_2") (pintype "passive"))
      (node (ref "C27") (pin "-") (pinfunction "-_-") (pintype "passive"))
      (node (ref "C28") (pin "-") (pinfunction "-_-") (pintype "passive"))
      (node (ref "C29") (pin "2") (pinfunction "2_2") (pintype "passive"))
      (node (ref "C3") (pin "2") (pinfunction "2_2") (pintype "passive"))
      (node (ref "C30") (pin "2") (pinfunction "2_2") (pintype "passive"))
      (node (ref "C31") (pin "-") (pinfunction "-_-") (pintype "passive"))
      (node (ref "C32") (pin "2") (pinfunction "2_2") (pintype "passive"))
      (node (ref "C34") (pin "2") (pinfunction "2_2") (pintype "passive"))
      (node (ref "C35") (pin "-") (pinfunction "-_-") (pintype "passive"))
      (node (ref "C38") (pin "2") (pinfunction "2_2") (pintype "passive"))
      (node (ref "C39") (pin "2") (pinfunction "2_2") (pintype "passive"))
      (node (ref "C4") (pin "-") (pinfunction "-_-") (pintype "passive"))
      (node (ref "C43") (pin "2") (pinfunction "2_2") (pintype "passive"))
      (node (ref "C44") (pin "2") (pinfunction "2_2") (pintype "passive"))
      (node (ref "C45") (pin "1") (pinfunction "1_1") (pintype "passive"))
      (node (ref "C46") (pin "1") (pinfunction "1_1") (pintype "passive"))
      (node (ref "C47") (pin "1") (pinfunction "1_1") (pintype "passive"))
      (node (ref "C48") (pin "1") (pinfunction "1_1") (pintype "passive"))
      (node (ref "C49") (pin "-") (pinfunction "-_-") (pintype "passive"))
      (node (ref "C5") (pin "2") (pinfunction "2_2") (pintype "passive"))
      (node (ref "C50") (pin "2") (pinfunction "2_2") (pintype "passive"))
      (node (ref "C6") (pin "1") (pinfunction "1_1") (pintype "passive"))
      (node (ref "C7") (pin "1") (pinfunction "1_1") (pintype "passive"))
      (node (ref "C8") (pin "2") (pinfunction "2_2") (pintype "passive"))
      (node (ref "DENS_POT") (pin "3") (pinfunction "3_3") (pintype "passive"))
      (node (ref "IC1") (pin "13") (pinfunction "G_13") (pintype "input"))
      (node (ref "IC1") (pin "8") (pinfunction "GND_8") (pintype "power_in"))
      (node (ref "IC10") (pin "3") (pinfunction "+IN_3") (pintype "input"))
      (node (ref "IC10") (pin "5") (pinfunction "+IN_5") (pintype "input"))
      (node (ref "IC2") (pin "1") (pinfunction "GND_1") (pintype "power_in"))
      (node (ref "IC3") (pin "3") (pinfunction "+IN_3") (pintype "input"))
      (node (ref "IC3") (pin "4") (pinfunction "V-_4") (pintype "power_in"))
      (node (ref "IC3") (pin "5") (pinfunction "+IN_5") (pintype "input"))
      (node (ref "IC4") (pin "10") (pinfunction "+IN_10") (pintype "input"))
      (node (ref "IC4") (pin "11") (pinfunction "V-_11") (pintype "power_in"))
      (node (ref "IC4") (pin "12") (pinfunction "+IN_12") (pintype "input"))
      (node (ref "IC4") (pin "3") (pinfunction "+IN_3") (pintype "input"))
      (node (ref "IC4") (pin "5") (pinfunction "+IN_5") (pintype "input"))
      (node (ref "IC5") (pin "12") (pinfunction "VSSA_12") (pintype "power_in"))
      (node (ref "IC5") (pin "18") (pinfunction "VSS_4_18") (pintype "power_in"))
      (node (ref "IC5") (pin "26") (pinfunction "PB0/ADC8/TIM3_CH3_26") (pintype "bidirectional"))
      (node (ref "IC5") (pin "28") (pinfunction "PB2/BOOT1_28") (pintype "bidirectional"))
      (node (ref "IC5") (pin "63") (pinfunction "VSS_3_63") (pintype "power_in"))
      (node (ref "IC6") (pin "1") (pinfunction "C_1") (pintype "passive"))
      (node (ref "IC7") (pin "1") (pinfunction "GND_1") (pintype "power_in"))
      (node (ref "IC8") (pin "11") (pinfunction "HPGND_11") (pintype "bidirectional"))
      (node (ref "IC8") (pin "15") (pinfunction "AGND_15") (pintype "bidirectional"))
      (node (ref "IC8") (pin "21") (pinfunction "MODE_21") (pintype "bidirectional"))
      (node (ref "IC8") (pin "22") (pinfunction "CSB_22") (pintype "bidirectional"))
      (node (ref "IC8") (pin "28") (pinfunction "DGND_28") (pintype "bidirectional"))
      (node (ref "IC9") (pin "3") (pinfunction "+IN_3") (pintype "input"))
      (node (ref "IC9") (pin "5") (pinfunction "+IN_5") (pintype "input"))
      (node (ref "IN-L") (pin "2") (pinfunction "2_2") (pintype "passive"))
      (node (ref "IN-R") (pin "2") (pinfunction "2_2") (pintype "passive"))
      (node (ref "JP1") (pin "1") (pinfunction "1_1") (pintype "passive"))
      (node (ref "JP2") (pin "3") (pinfunction "3_3") (pintype "passive"))
      (node (ref "JP2") (pin "5") (pinfunction "5_5") (pintype "passive"))
      (node (ref "JP2") (pin "9") (pinfunction "9_9") (pintype "passive"))
      (node (ref "LED1") (pin "2") (pinfunction "2_2") (pintype "passive"))
      (node (ref "LED2") (pin "2") (pinfunction "2_2") (pintype "passive"))
      (node (ref "LED3") (pin "2") (pinfunction "2_2") (pintype "passive"))
      (node (ref "LED4") (pin "2") (pinfunction "2_2") (pintype "passive"))
      (node (ref "OUT-L") (pin "2") (pinfunction "2_2") (pintype "passive"))
      (node (ref "OUT-R") (pin "2") (pinfunction "2_2") (pintype "passive"))
      (node (ref "POS_POT") (pin "3") (pinfunction "3_3") (pintype "passive"))
      (node (ref "POWER") (pin "2") (pinfunction "2_2") (pintype "passive"))
      (node (ref "POWER") (pin "3") (pinfunction "3_3") (pintype "passive"))
      (node (ref "Q1") (pin "E") (pinfunction "E_E") (pintype "passive"))
      (node (ref "Q2") (pin "E") (pinfunction "E_E") (pintype "passive"))
      (node (ref "R13") (pin "1") (pinfunction "1_1") (pintype "passive"))
      (node (ref "R50") (pin "1") (pinfunction "1_1") (pintype "passive"))
      (node (ref "R54") (pin "1") (pinfunction "1_1") (pintype "passive"))
      (node (ref "R56") (pin "1") (pinfunction "1_1") (pintype "passive"))
      (node (ref "R59") (pin "1") (pinfunction "1_1") (pintype "passive"))
      (node (ref "SPI") (pin "2") (pinfunction "2_2") (pintype "passive"))
      (node (ref "STPB_POTS") (pin "6") (pinfunction "6_6") (pintype "passive"))
      (node (ref "SW5") (pin "A") (pinfunction "P_A") (pintype "passive"))
      (node (ref "SW5") (pin "A'") (pinfunction "P1_A'") (pintype "passive"))
    )
    (net (code "9") (name "I2C_SCL") (class "Default")
      (node (ref "IC5") (pin "29") (pinfunction "PB10/SPI2_SCK/I2S_SCK/I2C2_SCL/USART3_TX_29") (pintype "bidirectional"))
      (node (ref "IC8") (pin "24") (pinfunction "SCLK_24") (pintype "bidirectional"))
      (node (ref "R40") (pin "1") (pinfunction "1_1") (pintype "passive"))
    )
    (net (code "10") (name "I2C_SDA") (class "Default")
      (node (ref "IC5") (pin "30") (pinfunction "PB11/I2C2_SDA/USART3_RX_30") (pintype "bidirectional"))
      (node (ref "IC8") (pin "23") (pinfunction "SDIN_23") (pintype "bidirectional"))
      (node (ref "R41") (pin "1") (pinfunction "1_1") (pintype "passive"))
    )
    (net (code "11") (name "I2S_LRCK") (class "Default")
      (node (ref "IC5") (pin "33") (pinfunction "PB12/SPI2_NSS/I2S2_WS/I2C2_SMBA/USART3_CK/TIM1_BKIN_33") (pintype "bidirectional"))
      (node (ref "IC8") (pin "5") (pinfunction "DACLRC_5") (pintype "bidirectional"))
      (node (ref "IC8") (pin "7") (pinfunction "ADCLRC_7") (pintype "bidirectional"))
    )
    (net (code "12") (name "I2S_SCK") (class "Default")
      (node (ref "IC5") (pin "34") (pinfunction "PB13/SPI2_SCK/I2S2_SCK/USART3_CTS/TIM1_CH1N_34") (pintype "bidirectional"))
      (node (ref "IC8") (pin "3") (pinfunction "BCLK_3") (pintype "bidirectional"))
    )
    (net (code "13") (name "I2S_SIN") (class "Default")
      (node (ref "IC5") (pin "35") (pinfunction "PB14/SPI2_MISO/USART3_RTS/TIM1_CH2N_35") (pintype "bidirectional"))
      (node (ref "IC8") (pin "6") (pinfunction "ADCDAT_6") (pintype "bidirectional"))
    )
    (net (code "14") (name "I2S_SOUT") (class "Default")
      (node (ref "IC5") (pin "36") (pinfunction "PB15/SPI2_MOSI/I2S2_SD/TIM1_CH3N_36") (pintype "bidirectional"))
      (node (ref "IC8") (pin "4") (pinfunction "DACDAT_4") (pintype "bidirectional"))
    )
    (net (code "15") (name "JTCK") (class "Default")
      (node (ref "IC5") (pin "49") (pinfunction "PA14/JTCK-SWCLK_49") (pintype "bidirectional"))
      (node (ref "JP2") (pin "4") (pinfunction "4_4") (pintype "passive"))
    )
    (net (code "16") (name "JTDI") (class "Default")
      (node (ref "IC5") (pin "50") (pinfunction "PA15/JTDI/SPI3_NSS/I2S3_WS_50") (pintype "bidirectional"))
      (node (ref "JP2") (pin "8") (pinfunction "8_8") (pintype "passive"))
    )
    (net (code "17") (name "JTDO") (class "Default")
      (node (ref "IC5") (pin "55") (pinfunction "PB3/JTDO/SPI3_SCK/I2S3_SCK_55") (pintype "bidirectional"))
      (node (ref "JP2") (pin "6") (pinfunction "6_6") (pintype "passive"))
    )
    (net (code "18") (name "JTMS") (class "Default")
      (node (ref "IC5") (pin "46") (pinfunction "PA13/JTMS-SWDAT_46") (pintype "bidirectional"))
      (node (ref "JP2") (pin "2") (pinfunction "2_2") (pintype "passive"))
    )
    (net (code "19") (name "LED_DATA") (class "Default")
      (node (ref "IC1") (pin "14") (pinfunction "SER_14") (pintype "input"))
      (node (ref "IC5") (pin "57") (pinfunction "PB5/I2C1_SMBA/SPI1_MOSI/SPI3_MOSI/I2S3_SD_57") (pintype "bidirectional"))
    )
    (net (code "20") (name "LED_EN") (class "Default")
      (node (ref "IC1") (pin "12") (pinfunction "RCK_12") (pintype "input"))
      (node (ref "ORIG_MAP") (pin "2") (pinfunction "2_2") (pintype "passive"))
    )
    (net (code "21") (name "LED_REC") (class "Default")
      (node (ref "IC5") (pin "62") (pinfunction "PB9/SPI2_NSS/I2S2_WS/I2C1_SDA/TIM4_CH4_62") (pintype "bidirectional"))
      (node (ref "R2") (pin "1") (pinfunction "1_1") (pintype "passive"))
    )
    (net (code "22") (name "LED_SCK") (class "Default")
      (node (ref "IC1") (pin "11") (pinfunction "SCK_11") (pintype "input"))
      (node (ref "ORIG_MAP") (pin "4") (pinfunction "4_4") (pintype "passive"))
    )
    (net (code "23") (name "LIN") (class "Default")
      (node (ref "C37") (pin "+") (pinfunction "+_+") (pintype "passive"))
      (node (ref "IC8") (pin "20") (pinfunction "LLINEIN_20") (pintype "bidirectional"))
    )
    (net (code "24") (name "LOUT") (class "Default")
      (node (ref "C33") (pin "+") (pinfunction "+_+") (pintype "passive"))
      (node (ref "IC8") (pin "12") (pinfunction "LOUT_12") (pintype "bidirectional"))
    )
    (net (code "25") (name "Net-(BLND_CV-Pad1)") (class "Default")
      (node (ref "BLND_CV") (pin "1") (pinfunction "1_1") (pintype "passive"))
      (node (ref "R39") (pin "2") (pinfunction "2_2") (pintype "passive"))
    )
    (net (code "26") (name "Net-(C33-Pad-)") (class "Default")
      (node (ref "C33") (pin "-") (pinfunction "-_-") (pintype "passive"))
      (node (ref "R51") (pin "2") (pinfunction "2_2") (pintype "passive"))
      (node (ref "R59") (pin "2") (pinfunction "2_2") (pintype "passive"))
    )
    (net (code "27") (name "Net-(C36-Pad-)") (class "Default")
      (node (ref "C36") (pin "-") (pinfunction "-_-") (pintype "passive"))
      (node (ref "C43") (pin "1") (pinfunction "1_1") (pintype "passive"))
      (node (ref "R53") (pin "1") (pinfunction "1_1") (pintype "passive"))
      (node (ref "R54") (pin "2") (pinfunction "2_2") (pintype "passive"))
    )
    (net (code "28") (name "Net-(C37-Pad-)") (class "Default")
      (node (ref "C37") (pin "-") (pinfunction "-_-") (pintype "passive"))
      (node (ref "C44") (pin "1") (pinfunction "1_1") (pintype "passive"))
      (node (ref "R55") (pin "1") (pinfunction "1_1") (pintype "passive"))
      (node (ref "R56") (pin "2") (pinfunction "2_2") (pintype "passive"))
    )
    (net (code "29") (name "Net-(C41-Pad-)") (class "Default")
      (node (ref "C41") (pin "-") (pinfunction "-_-") (pintype "passive"))
      (node (ref "R50") (pin "2") (pinfunction "2_2") (pintype "passive"))
      (node (ref "R52") (pin "2") (pinfunction "2_2") (pintype "passive"))
    )
    (net (code "30") (name "Net-(D1-PadA)") (class "Default")
      (node (ref "D1") (pin "A") (pinfunction "A_A") (pintype "passive"))
      (node (ref "POWER") (pin "1") (pinfunction "1_1") (pintype "passive"))
    )
    (net (code "31") (name "Net-(D2-PadC)") (class "Default")
      (node (ref "D2") (pin "C") (pinfunction "C_C") (pintype "passive"))
      (node (ref "POWER") (pin "4") (pinfunction "4_4") (pintype "passive"))
    )
    (net (code "32") (name "Net-(DENS_CV-Pad1)") (class "Default")
      (node (ref "DENS_CV") (pin "1") (pinfunction "1_1") (pintype "passive"))
      (node (ref "R32") (pin "2") (pinfunction "2_2") (pintype "passive"))
    )
    (net (code "33") (name "Net-(DENS_POT-Pad2)") (class "Default")
      (node (ref "DENS_POT") (pin "2") (pinfunction "2_2") (pintype "passive"))
      (node (ref "R33") (pin "2") (pinfunction "2_2") (pintype "passive"))
    )
    (net (code "34") (name "Net-(GAIN-Pad1)") (class "Default")
      (node (ref "GAIN") (pin "1") (pinfunction "1_1") (pintype "passive"))
      (node (ref "R47") (pin "1") (pinfunction "1_1") (pintype "passive"))
    )
    (net (code "35") (name "Net-(GAIN-Pad4)") (class "Default")
      (node (ref "GAIN") (pin "4") (pinfunction "4_4") (pintype "passive"))
      (node (ref "R46") (pin "1") (pinfunction "1_1") (pintype "passive"))
    )
    (net (code "36") (name "Net-(IC1A-QA)") (class "Default")
      (node (ref "IC1") (pin "15") (pinfunction "QA_15") (pintype "tri_state"))
      (node (ref "R10") (pin "2") (pinfunction "2_2") (pintype "passive"))
    )
    (net (code "37") (name "Net-(IC1A-QB)") (class "Default")
      (node (ref "IC1") (pin "1") (pinfunction "QB_1") (pintype "tri_state"))
      (node (ref "R9") (pin "2") (pinfunction "2_2") (pintype "passive"))
    )
    (net (code "38") (name "Net-(IC1A-QC)") (class "Default")
      (node (ref "IC1") (pin "2") (pinfunction "QC_2") (pintype "tri_state"))
      (node (ref "R8") (pin "2") (pinfunction "2_2") (pintype "passive"))
    )
    (net (code "39") (name "Net-(IC1A-QD)") (class "Default")
      (node (ref "IC1") (pin "3") (pinfunction "QD_3") (pintype "tri_state"))
      (node (ref "R7") (pin "2") (pinfunction "2_2") (pintype "passive"))
    )
    (net (code "40") (name "Net-(IC1A-QE)") (class "Default")
      (node (ref "IC1") (pin "4") (pinfunction "QE_4") (pintype "tri_state"))
      (node (ref "R6") (pin "2") (pinfunction "2_2") (pintype "passive"))
    )
    (net (code "41") (name "Net-(IC1A-QF)") (class "Default")
      (node (ref "IC1") (pin "5") (pinfunction "QF_5") (pintype "tri_state"))
      (node (ref "R5") (pin "2") (pinfunction "2_2") (pintype "passive"))
    )
    (net (code "42") (name "Net-(IC1A-QG)") (class "Default")
      (node (ref "IC1") (pin "6") (pinfunction "QG_6") (pintype "tri_state"))
      (node (ref "R3") (pin "2") (pinfunction "2_2") (pintype "passive"))
    )
    (net (code "43") (name "Net-(IC1A-QH)") (class "Default")
      (node (ref "IC1") (pin "7") (pinfunction "QH_7") (pintype "tri_state"))
      (node (ref "R4") (pin "2") (pinfunction "2_2") (pintype "passive"))
    )
    (net (code "44") (name "Net-(IC2-VIN)") (class "Default")
      (node (ref "C2") (pin "+") (pinfunction "+_+") (pintype "passive"))
      (node (ref "IC2") (pin "2") (pinfunction "VIN_2") (pintype "input"))
      (node (ref "R11") (pin "2") (pinfunction "2_2") (pintype "passive"))
    )
    (net (code "45") (name "Net-(IC3A--IN)") (class "Default")
      (node (ref "C22") (pin "1") (pinfunction "1_1") (pintype "passive"))
      (node (ref "IC3") (pin "2") (pinfunction "-IN_2") (pintype "input"))
      (node (ref "R31") (pin "2") (pinfunction "2_2") (pintype "passive"))
      (node (ref "R32") (pin "1") (pinfunction "1_1") (pintype "passive"))
      (node (ref "R33") (pin "1") (pinfunction "1_1") (pintype "passive"))
    )
    (net (code "46") (name "Net-(IC3B--IN)") (class "Default")
      (node (ref "C9") (pin "1") (pinfunction "1_1") (pintype "passive"))
      (node (ref "IC3") (pin "6") (pinfunction "-IN_6") (pintype "input"))
      (node (ref "R27") (pin "2") (pinfunction "2_2") (pintype "passive"))
      (node (ref "R28") (pin "1") (pinfunction "1_1") (pintype "passive"))
      (node (ref "R29") (pin "1") (pinfunction "1_1") (pintype "passive"))
    )
    (net (code "47") (name "Net-(IC4A--IN)") (class "Default")
      (node (ref "C20") (pin "1") (pinfunction "1_1") (pintype "passive"))
      (node (ref "IC4") (pin "2") (pinfunction "-IN_2") (pintype "input"))
      (node (ref "R34") (pin "2") (pinfunction "2_2") (pintype "passive"))
      (node (ref "R36") (pin "1") (pinfunction "1_1") (pintype "passive"))
      (node (ref "R38") (pin "1") (pinfunction "1_1") (pintype "passive"))
    )
    (net (code "48") (name "Net-(IC4B--IN)") (class "Default")
      (node (ref "C21") (pin "1") (pinfunction "1_1") (pintype "passive"))
      (node (ref "IC4") (pin "6") (pinfunction "-IN_6") (pintype "input"))
      (node (ref "R35") (pin "2") (pinfunction "2_2") (pintype "passive"))
      (node (ref "R37") (pin "1") (pinfunction "1_1") (pintype "passive"))
      (node (ref "R39") (pin "1") (pinfunction "1_1") (pintype "passive"))
    )
    (net (code "49") (name "Net-(IC4C--IN)") (class "Default")
      (node (ref "C11") (pin "1") (pinfunction "1_1") (pintype "passive"))
      (node (ref "IC4") (pin "9") (pinfunction "-IN_9") (pintype "input"))
      (node (ref "R23") (pin "1") (pinfunction "1_1") (pintype "passive"))
      (node (ref "R24") (pin "1") (pinfunction "1_1") (pintype "passive"))
      (node (ref "R26") (pin "2") (pinfunction "2_2") (pintype "passive"))
    )
    (net (code "50") (name "Net-(IC4D--IN)") (class "Default")
      (node (ref "C10") (pin "1") (pinfunction "1_1") (pintype "passive"))
      (node (ref "IC4") (pin "13") (pinfunction "-IN_13") (pintype "input"))
      (node (ref "R21") (pin "1") (pinfunction "1_1") (pintype "passive"))
      (node (ref "R22") (pin "1") (pinfunction "1_1") (pintype "passive"))
      (node (ref "R25") (pin "2") (pinfunction "2_2") (pintype "passive"))
    )
    (net (code "51") (name "Net-(IC5-PD0{slash}OSC_IN)") (class "Default")
      (node (ref "C7") (pin "2") (pinfunction "2_2") (pintype "passive"))
      (node (ref "IC5") (pin "5") (pinfunction "PD0/OSC_IN_5") (pintype "bidirectional"))
      (node (ref "Q3") (pin "2") (pinfunction "2_2") (pintype "passive"))
    )
    (net (code "52") (name "Net-(IC5-PD1{slash}OSC_OUT)") (class "Default")
      (node (ref "C6") (pin "2") (pinfunction "2_2") (pintype "passive"))
      (node (ref "IC5") (pin "6") (pinfunction "PD1/OSC_OUT_6") (pintype "bidirectional"))
      (node (ref "Q3") (pin "1") (pinfunction "1_1") (pintype "passive"))
    )
    (net (code "53") (name "Net-(IC5-VCAP_1)") (class "Default")
      (node (ref "C24") (pin "1") (pinfunction "1_1") (pintype "passive"))
      (node (ref "IC5") (pin "31") (pinfunction "VCAP_1_31") (pintype "power_in"))
    )
    (net (code "54") (name "Net-(IC5-VCAP_2)") (class "Default")
      (node (ref "C19") (pin "1") (pinfunction "1_1") (pintype "passive"))
      (node (ref "IC5") (pin "47") (pinfunction "VCAP_2_47") (pintype "power_in"))
    )
    (net (code "55") (name "Net-(IC8-VMID)") (class "Default")
      (node (ref "C34") (pin "1") (pinfunction "1_1") (pintype "passive"))
      (node (ref "C35") (pin "+") (pinfunction "+_+") (pintype "passive"))
      (node (ref "IC8") (pin "16") (pinfunction "VMID_16") (pintype "bidirectional"))
    )
    (net (code "56") (name "Net-(IC8-XTI{slash}MCLK)") (class "Default")
      (node (ref "C48") (pin "2") (pinfunction "2_2") (pintype "passive"))
      (node (ref "IC8") (pin "25") (pinfunction "XTI/MCLK_25") (pintype "bidirectional"))
      (node (ref "Q4") (pin "2") (pinfunction "2_2") (pintype "passive"))
    )
    (net (code "57") (name "Net-(IC8-XTO)") (class "Default")
      (node (ref "C47") (pin "2") (pinfunction "2_2") (pintype "passive"))
      (node (ref "IC8") (pin "26") (pinfunction "XTO_26") (pintype "bidirectional"))
      (node (ref "Q4") (pin "1") (pinfunction "1_1") (pintype "passive"))
    )
    (net (code "58") (name "Net-(IC9A--IN)") (class "Default")
      (node (ref "IC9") (pin "2") (pinfunction "-IN_2") (pintype "input"))
      (node (ref "R46") (pin "2") (pinfunction "2_2") (pintype "passive"))
      (node (ref "R57") (pin "1") (pinfunction "1_1") (pintype "passive"))
    )
    (net (code "59") (name "Net-(IC9A-OUT)") (class "Default")
      (node (ref "GAIN") (pin "3") (pinfunction "3_3") (pintype "passive"))
      (node (ref "IC9") (pin "1") (pinfunction "OUT_1") (pintype "output"))
      (node (ref "R55") (pin "2") (pinfunction "2_2") (pintype "passive"))
    )
    (net (code "60") (name "Net-(IC9B--IN)") (class "Default")
      (node (ref "IC9") (pin "6") (pinfunction "-IN_6") (pintype "input"))
      (node (ref "R47") (pin "2") (pinfunction "2_2") (pintype "passive"))
      (node (ref "R58") (pin "1") (pinfunction "1_1") (pintype "passive"))
    )
    (net (code "61") (name "Net-(IC9B-OUT)") (class "Default")
      (node (ref "GAIN") (pin "2") (pinfunction "2_2") (pintype "passive"))
      (node (ref "IC9") (pin "7") (pinfunction "OUT_7") (pintype "output"))
      (node (ref "R53") (pin "2") (pinfunction "2_2") (pintype "passive"))
    )
    (net (code "62") (name "Net-(IC10A--IN)") (class "Default")
      (node (ref "C40") (pin "1") (pinfunction "1_1") (pintype "passive"))
      (node (ref "IC10") (pin "2") (pinfunction "-IN_2") (pintype "input"))
      (node (ref "R49") (pin "2") (pinfunction "2_2") (pintype "passive"))
      (node (ref "R51") (pin "1") (pinfunction "1_1") (pintype "passive"))
    )
    (net (code "63") (name "Net-(IC10A-OUT)") (class "Default")
      (node (ref "C40") (pin "2") (pinfunction "2_2") (pintype "passive"))
      (node (ref "IC10") (pin "1") (pinfunction "OUT_1") (pintype "output"))
      (node (ref "R49") (pin "1") (pinfunction "1_1") (pintype "passive"))
      (node (ref "R61") (pin "2") (pinfunction "2_2") (pintype "passive"))
    )
    (net (code "64") (name "Net-(IC10B--IN)") (class "Default")
      (node (ref "C42") (pin "1") (pinfunction "1_1") (pintype "passive"))
      (node (ref "IC10") (pin "6") (pinfunction "-IN_6") (pintype "input"))
      (node (ref "R48") (pin "2") (pinfunction "2_2") (pintype "passive"))
      (node (ref "R52") (pin "1") (pinfunction "1_1") (pintype "passive"))
    )
    (net (code "65") (name "Net-(IC10B-OUT)") (class "Default")
      (node (ref "C42") (pin "2") (pinfunction "2_2") (pintype "passive"))
      (node (ref "IC10") (pin "7") (pinfunction "OUT_7") (pintype "output"))
      (node (ref "R48") (pin "1") (pinfunction "1_1") (pintype "passive"))
      (node (ref "R62") (pin "2") (pinfunction "2_2") (pintype "passive"))
    )
    (net (code "66") (name "Net-(IN-L-Pad1)") (class "Default")
      (node (ref "IN-L") (pin "1") (pinfunction "1_1") (pintype "passive"))
      (node (ref "R57") (pin "2") (pinfunction "2_2") (pintype "passive"))
    )
    (net (code "67") (name "Net-(IN-R-Pad1)") (class "Default")
      (node (ref "IN-R") (pin "1") (pinfunction "1_1") (pintype "passive"))
      (node (ref "R58") (pin "2") (pinfunction "2_2") (pintype "passive"))
    )
    (net (code "68") (name "Net-(LED1-Pad1)") (class "Default")
      (node (ref "LED1") (pin "1") (pinfunction "1_1") (pintype "passive"))
      (node (ref "R10") (pin "1") (pinfunction "1_1") (pintype "passive"))
    )
    (net (code "69") (name "Net-(LED1-Pad3)") (class "Default")
      (node (ref "LED1") (pin "3") (pinfunction "3_3") (pintype "passive"))
      (node (ref "R9") (pin "1") (pinfunction "1_1") (pintype "passive"))
    )
    (net (code "70") (name "Net-(LED2-Pad1)") (class "Default")
      (node (ref "LED2") (pin "1") (pinfunction "1_1") (pintype "passive"))
      (node (ref "R8") (pin "1") (pinfunction "1_1") (pintype "passive"))
    )
    (net (code "71") (name "Net-(LED2-Pad3)") (class "Default")
      (node (ref "LED2") (pin "3") (pinfunction "3_3") (pintype "passive"))
      (node (ref "R7") (pin "1") (pinfunction "1_1") (pintype "passive"))
    )
    (net (code "72") (name "Net-(LED3-Pad1)") (class "Default")
      (node (ref "LED3") (pin "1") (pinfunction "1_1") (pintype "passive"))
      (node (ref "R6") (pin "1") (pinfunction "1_1") (pintype "passive"))
    )
    (net (code "73") (name "Net-(LED3-Pad3)") (class "Default")
      (node (ref "LED3") (pin "3") (pinfunction "3_3") (pintype "passive"))
      (node (ref "R5") (pin "1") (pinfunction "1_1") (pintype "passive"))
    )
    (net (code "74") (name "Net-(LED4-Pad1)") (class "Default")
      (node (ref "LED4") (pin "1") (pinfunction "1_1") (pintype "passive"))
      (node (ref "R3") (pin "1") (pinfunction "1_1") (pintype "passive"))
    )
    (net (code "75") (name "Net-(LED4-Pad3)") (class "Default")
      (node (ref "LED4") (pin "3") (pinfunction "3_3") (pintype "passive"))
      (node (ref "R4") (pin "1") (pinfunction "1_1") (pintype "passive"))
    )
    (net (code "76") (name "Net-(OUT-L-Pad1)") (class "Default")
      (node (ref "OUT-L") (pin "1") (pinfunction "1_1") (pintype "passive"))
      (node (ref "R61") (pin "1") (pinfunction "1_1") (pintype "passive"))
    )
    (net (code "77") (name "Net-(OUT-R-Pad1)") (class "Default")
      (node (ref "OUT-R") (pin "1") (pinfunction "1_1") (pintype "passive"))
      (node (ref "R62") (pin "1") (pinfunction "1_1") (pintype "passive"))
    )
    (net (code "78") (name "Net-(POS_CV-Pad1)") (class "Default")
      (node (ref "POS_CV") (pin "1") (pinfunction "1_1") (pintype "passive"))
      (node (ref "R29") (pin "2") (pinfunction "2_2") (pintype "passive"))
    )
    (net (code "79") (name "Net-(POS_POT-Pad2)") (class "Default")
      (node (ref "POS_POT") (pin "2") (pinfunction "2_2") (pintype "passive"))
      (node (ref "R28") (pin "2") (pinfunction "2_2") (pintype "passive"))
    )
    (net (code "80") (name "Net-(Q1-PadB)") (class "Default")
      (node (ref "Q1") (pin "B") (pinfunction "B_B") (pintype "passive"))
      (node (ref "R12") (pin "2") (pinfunction "2_2") (pintype "passive"))
    )
    (net (code "81") (name "Net-(Q2-PadB)") (class "Default")
      (node (ref "Q2") (pin "B") (pinfunction "B_B") (pintype "passive"))
      (node (ref "R15") (pin "2") (pinfunction "2_2") (pintype "passive"))
    )
    (net (code "82") (name "Net-(R2-Pad2)") (class "Default")
      (node (ref "R2") (pin "2") (pinfunction "2_2") (pintype "passive"))
      (node (ref "REC_LED-BTN") (pin "1") (pinfunction "1_1") (pintype "passive"))
    )
    (net (code "83") (name "Net-(R12-Pad1)") (class "Default")
      (node (ref "R12") (pin "1") (pinfunction "1_1") (pintype "passive"))
      (node (ref "RP_TRIG") (pin "1") (pinfunction "1_1") (pintype "passive"))
    )
    (net (code "84") (name "Net-(R15-Pad1)") (class "Default")
      (node (ref "R15") (pin "1") (pinfunction "1_1") (pintype "passive"))
      (node (ref "RP_TRIG") (pin "2") (pinfunction "2_2") (pintype "passive"))
    )
    (net (code "85") (name "Net-(R21-Pad2)") (class "Default")
      (node (ref "R21") (pin "2") (pinfunction "2_2") (pintype "passive"))
      (node (ref "SIZE_CV") (pin "1") (pinfunction "1_1") (pintype "passive"))
    )
    (net (code "86") (name "Net-(R24-Pad2)") (class "Default")
      (node (ref "R24") (pin "2") (pinfunction "2_2") (pintype "passive"))
      (node (ref "TEXT_CV") (pin "1") (pinfunction "1_1") (pintype "passive"))
    )
    (net (code "87") (name "Net-(R38-Pad2)") (class "Default")
      (node (ref "R38") (pin "2") (pinfunction "2_2") (pintype "passive"))
      (node (ref "V_OCT") (pin "1") (pinfunction "1_1") (pintype "passive"))
    )
    (net (code "88") (name "PA4") (class "Default")
      (node (ref "IC5") (pin "20") (pinfunction "PA4/SPI1_NSS/SPI3_NSS/USART2_CK/I2S3_WS/ADC4/DAC1_20") (pintype "bidirectional"))
      (node (ref "ORIG_MAP") (pin "5") (pinfunction "5_5") (pintype "passive"))
      (node (ref "SPI") (pin "3") (pinfunction "3_3") (pintype "passive"))
    )
    (net (code "89") (name "PA5") (class "Default")
      (node (ref "IC5") (pin "21") (pinfunction "PA5/SPI1_SCK/ADC5/DAC2_21") (pintype "bidirectional"))
      (node (ref "ORIG_MAP") (pin "7") (pinfunction "7_7") (pintype "passive"))
      (node (ref "SPI") (pin "4") (pinfunction "4_4") (pintype "passive"))
    )
    (net (code "90") (name "PA6") (class "Default")
      (node (ref "IC5") (pin "22") (pinfunction "PA6/SPI1_MISO/ADC6/TIM3_CH1_22") (pintype "bidirectional"))
      (node (ref "ORIG_MAP") (pin "9") (pinfunction "9_9") (pintype "passive"))
      (node (ref "SPI") (pin "5") (pinfunction "5_5") (pintype "passive"))
    )
    (net (code "91") (name "PA7") (class "Default")
      (node (ref "IC5") (pin "23") (pinfunction "PA7/SPI1_MOSI/ADC7/TIM3_CH2_23") (pintype "bidirectional"))
      (node (ref "ORIG_MAP") (pin "11") (pinfunction "11_11") (pintype "passive"))
      (node (ref "SPI") (pin "6") (pinfunction "6_6") (pintype "passive"))
    )
    (net (code "92") (name "PC2") (class "Default")
      (node (ref "IC5") (pin "10") (pinfunction "PC2/SPI2_MISO/ADC12_10") (pintype "bidirectional"))
      (node (ref "NEW_MAP") (pin "3") (pinfunction "3_3") (pintype "passive"))
    )
    (net (code "93") (name "PC3") (class "Default")
      (node (ref "IC5") (pin "11") (pinfunction "PC3/SPI2_MOSI/I2S2_SD/ADC13_11") (pintype "bidirectional"))
      (node (ref "NEW_MAP") (pin "4") (pinfunction "4_4") (pintype "passive"))
    )
    (net (code "94") (name "PC4") (class "Default")
      (node (ref "IC5") (pin "24") (pinfunction "PC4/ADC14_24") (pintype "bidirectional"))
      (node (ref "NEW_MAP") (pin "5") (pinfunction "5_5") (pintype "passive"))
      (node (ref "ORIG_MAP") (pin "1") (pinfunction "1_1") (pintype "passive"))
    )
    (net (code "95") (name "PC5") (class "Default")
      (node (ref "IC5") (pin "25") (pinfunction "PC5/ADC15_25") (pintype "bidirectional"))
      (node (ref "NEW_MAP") (pin "6") (pinfunction "6_6") (pintype "passive"))
      (node (ref "ORIG_MAP") (pin "3") (pinfunction "3_3") (pintype "passive"))
    )
    (net (code "96") (name "PC6") (class "Default")
      (node (ref "IC5") (pin "37") (pinfunction "PC6/I2S2_MCK_37") (pintype "bidirectional"))
      (node (ref "NEW_MAP") (pin "1") (pinfunction "1_1") (pintype "passive"))
    )
    (net (code "97") (name "PC7") (class "Default")
      (node (ref "IC5") (pin "38") (pinfunction "PC7/I2S3_MCK_38") (pintype "bidirectional"))
      (node (ref "NEW_MAP") (pin "2") (pinfunction "2_2") (pintype "passive"))
    )
    (net (code "98") (name "PITCH_POT") (class "Default")
      (node (ref "IC5") (pin "9") (pinfunction "PC1/ADC11_9") (pintype "bidirectional"))
      (node (ref "STPB_POTS") (pin "4") (pinfunction "4_4") (pintype "passive"))
    )
    (net (code "99") (name "PLAY") (class "Default")
      (node (ref "IC5") (pin "58") (pinfunction "PB6/I2C1_SCL/TIM4_CH1/USART1_TX_58") (pintype "bidirectional"))
      (node (ref "Q2") (pin "C") (pinfunction "C_C") (pintype "passive"))
      (node (ref "R16") (pin "1") (pinfunction "1_1") (pintype "passive"))
    )
    (net (code "100") (name "POSITION_POT_CV") (class "Default")
      (node (ref "C9") (pin "2") (pinfunction "2_2") (pintype "passive"))
      (node (ref "IC3") (pin "7") (pinfunction "OUT_7") (pintype "output"))
      (node (ref "IC5") (pin "16") (pinfunction "PA2/USART2_TX/ADC2/TIM2_CH3_16") (pintype "bidirectional"))
      (node (ref "R27") (pin "1") (pinfunction "1_1") (pintype "passive"))
    )
    (net (code "101") (name "REC") (class "Default")
      (node (ref "IC5") (pin "59") (pinfunction "PB7/I2C1_SDA/TIM4_CH2/USART1_RX_59") (pintype "bidirectional"))
      (node (ref "Q1") (pin "C") (pinfunction "C_C") (pintype "passive"))
      (node (ref "R14") (pin "1") (pinfunction "1_1") (pintype "passive"))
    )
    (net (code "102") (name "RESET") (class "Default")
      (node (ref "IC5") (pin "7") (pinfunction "NRST_7") (pintype "bidirectional"))
      (node (ref "JP2") (pin "10") (pinfunction "10_10") (pintype "passive"))
      (node (ref "R17") (pin "1") (pinfunction "1_1") (pintype "passive"))
      (node (ref "SW5") (pin "B") (pinfunction "S_B") (pintype "passive"))
      (node (ref "SW5") (pin "B'") (pinfunction "S1_B'") (pintype "passive"))
    )
    (net (code "103") (name "RIN") (class "Default")
      (node (ref "C36") (pin "+") (pinfunction "+_+") (pintype "passive"))
      (node (ref "IC8") (pin "19") (pinfunction "RLINEIN_19") (pintype "bidirectional"))
    )
    (net (code "104") (name "ROUT") (class "Default")
      (node (ref "C41") (pin "+") (pinfunction "+_+") (pintype "passive"))
      (node (ref "IC8") (pin "13") (pinfunction "ROUT_13") (pintype "bidirectional"))
    )
    (net (code "105") (name "RX") (class "Default")
      (node (ref "IC5") (pin "43") (pinfunction "PA10/USART1_RX/TIM1_CH3_43") (pintype "bidirectional"))
      (node (ref "JP1") (pin "4") (pinfunction "4_4") (pintype "passive"))
    )
    (net (code "106") (name "SIZE_CV") (class "Default")
      (node (ref "C10") (pin "2") (pinfunction "2_2") (pintype "passive"))
      (node (ref "IC4") (pin "14") (pinfunction "OUT_14") (pintype "output"))
      (node (ref "IC5") (pin "15") (pinfunction "PA1/USART2_RTS/UART4_RX/ADC1/TIM2_CH2_15") (pintype "bidirectional"))
      (node (ref "R25") (pin "1") (pinfunction "1_1") (pintype "passive"))
    )
    (net (code "107") (name "SIZE_POT") (class "Default")
      (node (ref "IC5") (pin "8") (pinfunction "PC0/ADC10_8") (pintype "bidirectional"))
      (node (ref "STPB_POTS") (pin "2") (pinfunction "2_2") (pintype "passive"))
    )
    (net (code "108") (name "SW_LOAD") (class "Default")
      (node (ref "IC5") (pin "51") (pinfunction "PC10/SPI3_SCK/I2S3_SCK/UART4_TX_51") (pintype "bidirectional"))
      (node (ref "ML_BTN") (pin "2") (pinfunction "2_2") (pintype "passive"))
    )
    (net (code "109") (name "SW_MODE") (class "Default")
      (node (ref "IC5") (pin "52") (pinfunction "PC11/UART4_RX/SPI3_MISO/USART3_RX_52") (pintype "bidirectional"))
      (node (ref "ML_BTN") (pin "1") (pinfunction "1_1") (pintype "passive"))
    )
    (net (code "110") (name "SW_REC") (class "Default")
      (node (ref "IC5") (pin "61") (pinfunction "PB8/TIM4_CH3/I2C1_SCL_61") (pintype "bidirectional"))
      (node (ref "REC_LED-BTN") (pin "2") (pinfunction "2_2") (pintype "passive"))
    )
    (net (code "111") (name "TEXTURE_CV") (class "Default")
      (node (ref "C11") (pin "2") (pinfunction "2_2") (pintype "passive"))
      (node (ref "IC4") (pin "8") (pinfunction "OUT_8") (pintype "output"))
      (node (ref "IC5") (pin "14") (pinfunction "PA0-WKUP/USART2_CTS/UART4_TX/ADC0/TIM2_CH1_ETR_14") (pintype "bidirectional"))
      (node (ref "R26") (pin "1") (pinfunction "1_1") (pintype "passive"))
    )
    (net (code "112") (name "TEXTURE_POT") (class "Default")
      (node (ref "ORIG_MAP") (pin "10") (pinfunction "10_10") (pintype "passive"))
      (node (ref "STPB_POTS") (pin "3") (pinfunction "3_3") (pintype "passive"))
    )
    (net (code "113") (name "TX") (class "Default")
      (node (ref "IC5") (pin "42") (pinfunction "PA9/USART1_TX/TIM1_CH2_42") (pintype "bidirectional"))
      (node (ref "JP1") (pin "5") (pinfunction "5_5") (pintype "passive"))
    )
    (net (code "114") (name "VBAT") (class "Default")
      (node (ref "IC5") (pin "1") (pinfunction "VBAT_1") (pintype "power_in"))
    )
    (net (code "115") (name "VCC") (class "Default")
      (node (ref "C1") (pin "+") (pinfunction "+_+") (pintype "passive"))
      (node (ref "C38") (pin "1") (pinfunction "1_1") (pintype "passive"))
      (node (ref "C39") (pin "1") (pinfunction "1_1") (pintype "passive"))
      (node (ref "D1") (pin "C") (pinfunction "C_C") (pintype "passive"))
      (node (ref "IC10") (pin "8") (pinfunction "V+_8") (pintype "power_in"))
      (node (ref "IC7") (pin "3") (pinfunction "VIN_3") (pintype "input"))
      (node (ref "IC9") (pin "8") (pinfunction "V+_8") (pintype "power_in"))
      (node (ref "R11") (pin "1") (pinfunction "1_1") (pintype "passive"))
    )
    (net (code "116") (name "VEE") (class "Default")
      (node (ref "C13") (pin "-") (pinfunction "-_-") (pintype "passive"))
      (node (ref "C45") (pin "2") (pinfunction "2_2") (pintype "passive"))
      (node (ref "C46") (pin "2") (pinfunction "2_2") (pintype "passive"))
      (node (ref "D2") (pin "A") (pinfunction "A_A") (pintype "passive"))
      (node (ref "IC10") (pin "4") (pinfunction "V-_4") (pintype "power_in"))
      (node (ref "IC9") (pin "4") (pinfunction "V-_4") (pintype "power_in"))
      (node (ref "R30") (pin "1") (pinfunction "1_1") (pintype "passive"))
    )
    (net (code "117") (name "V_OCT") (class "Default")
      (node (ref "C20") (pin "2") (pinfunction "2_2") (pintype "passive"))
      (node (ref "IC4") (pin "1") (pinfunction "OUT_1") (pintype "output"))
      (node (ref "ORIG_MAP") (pin "6") (pinfunction "6_6") (pintype "passive"))
      (node (ref "R34") (pin "1") (pinfunction "1_1") (pintype "passive"))
    )
    (net (code "118") (name "unconnected-(IC1A-QH*-Pad9)") (class "Default")
      (node (ref "IC1") (pin "9") (pinfunction "QH*_9") (pintype "tri_state"))
    )
    (net (code "119") (name "unconnected-(IC5-PA8{slash}USART1_CK{slash}TIM1_CH1{slash}MCO-Pad41)") (class "Default")
      (node (ref "IC5") (pin "41") (pinfunction "PA8/USART1_CK/TIM1_CH1/MCO_41") (pintype "bidirectional"))
    )
    (net (code "120") (name "unconnected-(IC5-PA11{slash}USART1_CTS{slash}CANRX{slash}USBDM{slash}TIM1_CH4-Pad44)") (class "Default")
      (node (ref "IC5") (pin "44") (pinfunction "PA11/USART1_CTS/CANRX/USBDM/TIM1_CH4_44") (pintype "bidirectional"))
    )
    (net (code "121") (name "unconnected-(IC5-PA12{slash}USART1_RTS{slash}CANTX{slash}USBDP{slash}TIM1_ETR-Pad45)") (class "Default")
      (node (ref "IC5") (pin "45") (pinfunction "PA12/USART1_RTS/CANTX/USBDP/TIM1_ETR_45") (pintype "bidirectional"))
    )
    (net (code "122") (name "unconnected-(IC5-PB1{slash}ADC9{slash}TIM3_CH4-Pad27)") (class "Default")
      (node (ref "IC5") (pin "27") (pinfunction "PB1/ADC9/TIM3_CH4_27") (pintype "bidirectional"))
    )
    (net (code "123") (name "unconnected-(IC5-PB4{slash}NJTRST{slash}SPI3_MISO{slash}SPI1_MISO-Pad56)") (class "Default")
      (node (ref "IC5") (pin "56") (pinfunction "PB4/NJTRST/SPI3_MISO/SPI1_MISO_56") (pintype "bidirectional"))
    )
    (net (code "124") (name "unconnected-(IC5-PC8-Pad39)") (class "Default")
      (node (ref "IC5") (pin "39") (pinfunction "PC8_39") (pintype "bidirectional"))
    )
    (net (code "125") (name "unconnected-(IC5-PC9{slash}I2S2_CKIN{slash}I2S3_CKIN-Pad40)") (class "Default")
      (node (ref "IC5") (pin "40") (pinfunction "PC9/I2S2_CKIN/I2S3_CKIN_40") (pintype "bidirectional"))
    )
    (net (code "126") (name "unconnected-(IC5-PC12{slash}UART5_TX{slash}I2S3_SD{slash}USART3_CK-Pad53)") (class "Default")
      (node (ref "IC5") (pin "53") (pinfunction "PC12/UART5_TX/I2S3_SD/USART3_CK_53") (pintype "bidirectional"))
    )
    (net (code "127") (name "unconnected-(IC5-PC13-TAMPER-RTC-Pad2)") (class "Default")
      (node (ref "IC5") (pin "2") (pinfunction "PC13-TAMPER-RTC_2") (pintype "bidirectional"))
    )
    (net (code "128") (name "unconnected-(IC5-PC14{slash}OSC32_IN-Pad3)") (class "Default")
      (node (ref "IC5") (pin "3") (pinfunction "PC14/OSC32_IN_3") (pintype "bidirectional"))
    )
    (net (code "129") (name "unconnected-(IC5-PC15{slash}OSC_OUT-Pad4)") (class "Default")
      (node (ref "IC5") (pin "4") (pinfunction "PC15/OSC_OUT_4") (pintype "bidirectional"))
    )
    (net (code "130") (name "unconnected-(IC5-PD2{slash}TIM3-ETR-Pad54)") (class "Default")
      (node (ref "IC5") (pin "54") (pinfunction "PD2/TIM3-ETR_54") (pintype "bidirectional"))
    )
    (net (code "131") (name "unconnected-(IC8-CLKOUT-Pad2)") (class "Default")
      (node (ref "IC8") (pin "2") (pinfunction "CLKOUT_2") (pintype "bidirectional"))
    )
    (net (code "132") (name "unconnected-(IC8-LHPOUT-Pad9)") (class "Default")
      (node (ref "IC8") (pin "9") (pinfunction "LHPOUT_9") (pintype "bidirectional"))
    )
    (net (code "133") (name "unconnected-(IC8-MICBIAS-Pad17)") (class "Default")
      (node (ref "IC8") (pin "17") (pinfunction "MICBIAS_17") (pintype "bidirectional"))
    )
    (net (code "134") (name "unconnected-(IC8-MICIN-Pad18)") (class "Default")
      (node (ref "IC8") (pin "18") (pinfunction "MICIN_18") (pintype "bidirectional"))
    )
    (net (code "135") (name "unconnected-(IC8-RHPOUT-Pad10)") (class "Default")
      (node (ref "IC8") (pin "10") (pinfunction "RHPOUT_10") (pintype "bidirectional"))
    )
    (net (code "136") (name "unconnected-(JP1-Pad2)") (class "Default")
      (node (ref "JP1") (pin "2") (pinfunction "2_2") (pintype "passive"))
    )
    (net (code "137") (name "unconnected-(JP1-Pad3)") (class "Default")
      (node (ref "JP1") (pin "3") (pinfunction "3_3") (pintype "passive"))
    )
    (net (code "138") (name "unconnected-(JP1-Pad6)") (class "Default")
      (node (ref "JP1") (pin "6") (pinfunction "6_6") (pintype "passive"))
    )
    (net (code "139") (name "unconnected-(JP2-Pad7)") (class "Default")
      (node (ref "JP2") (pin "7") (pinfunction "7_7") (pintype "passive"))
    )
  )
)
